# PDB_Sheet2.net
KiCad netlist of a schematic drawn in Altium Designer
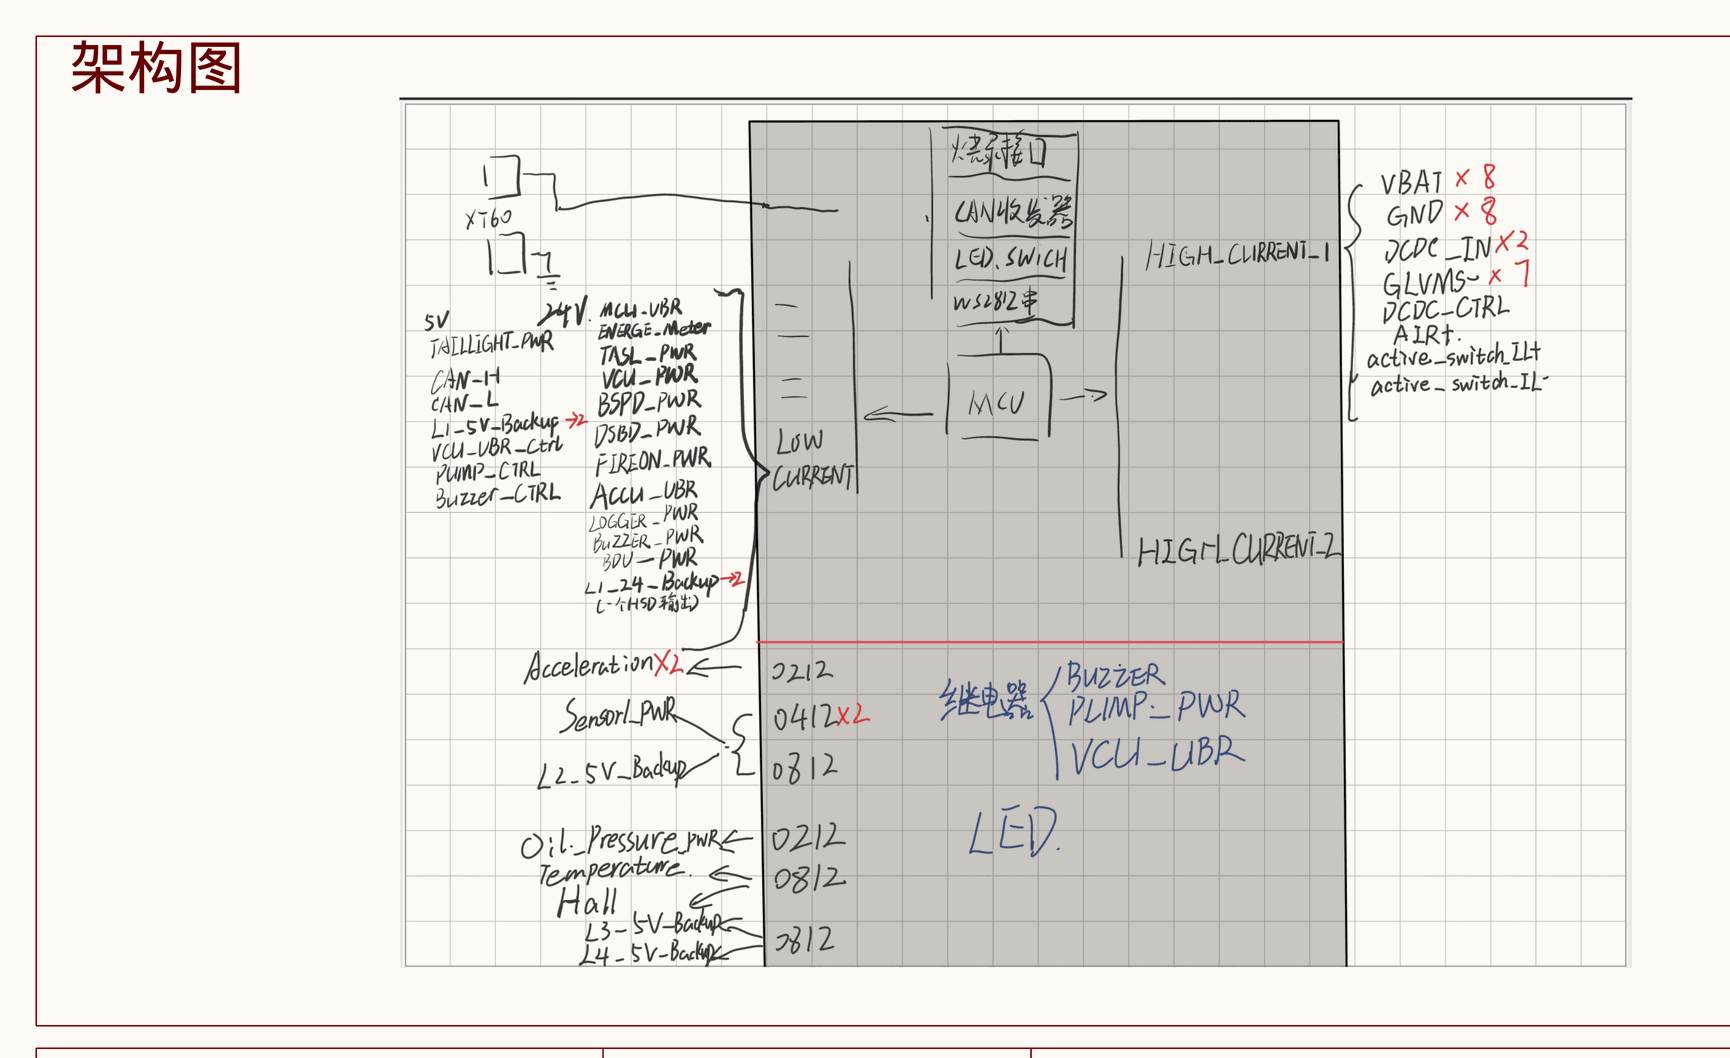
[diagram p0: PDB_Sheet2.SchDoc, top left]
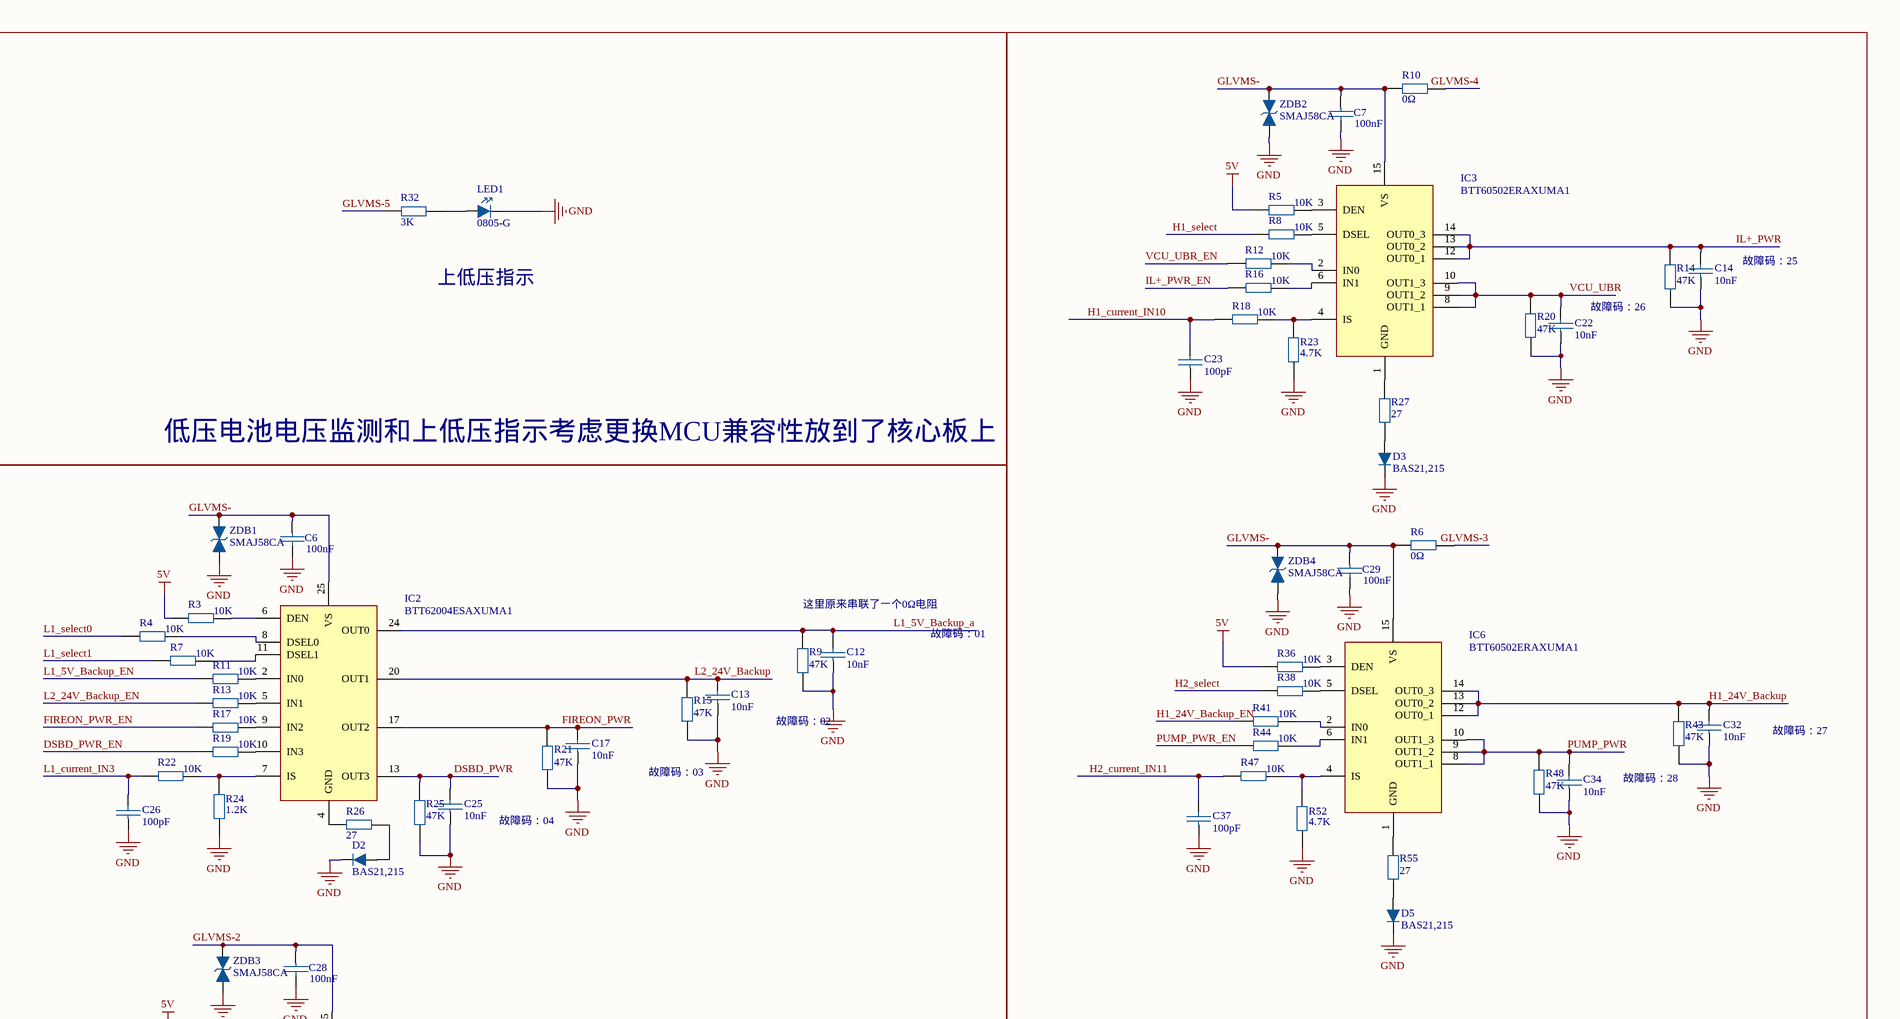
[diagram p1: PDB_Sheet2.SchDoc, top right]
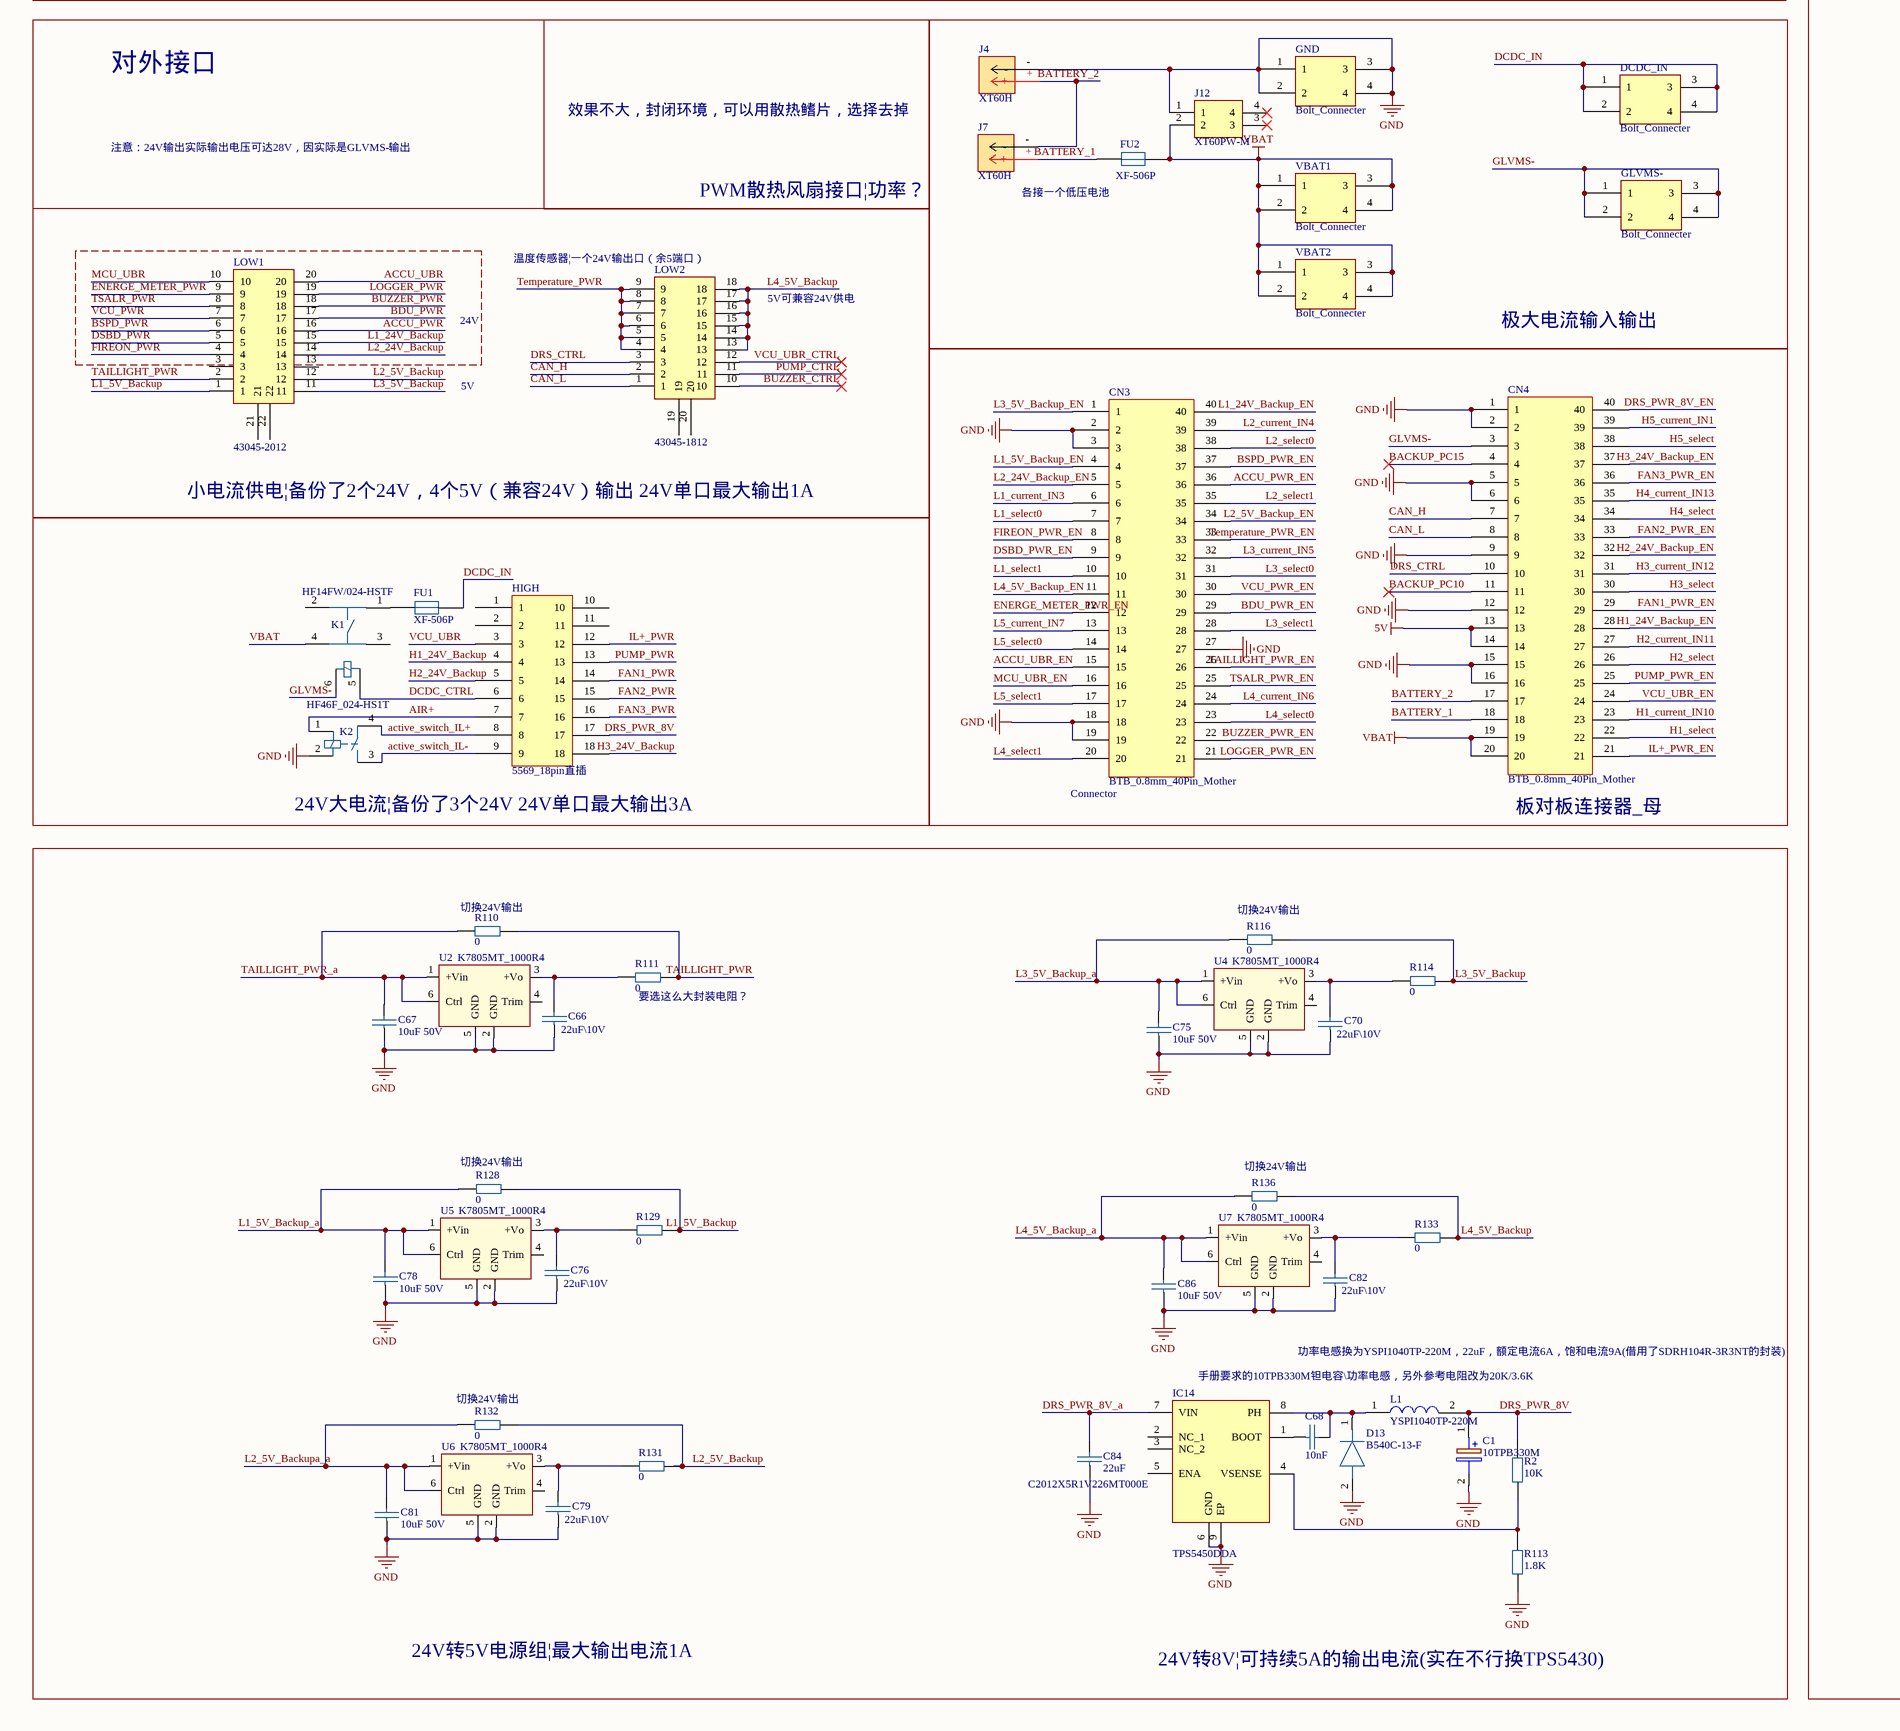
[diagram p2: PDB_Sheet2.SchDoc, bottom left]
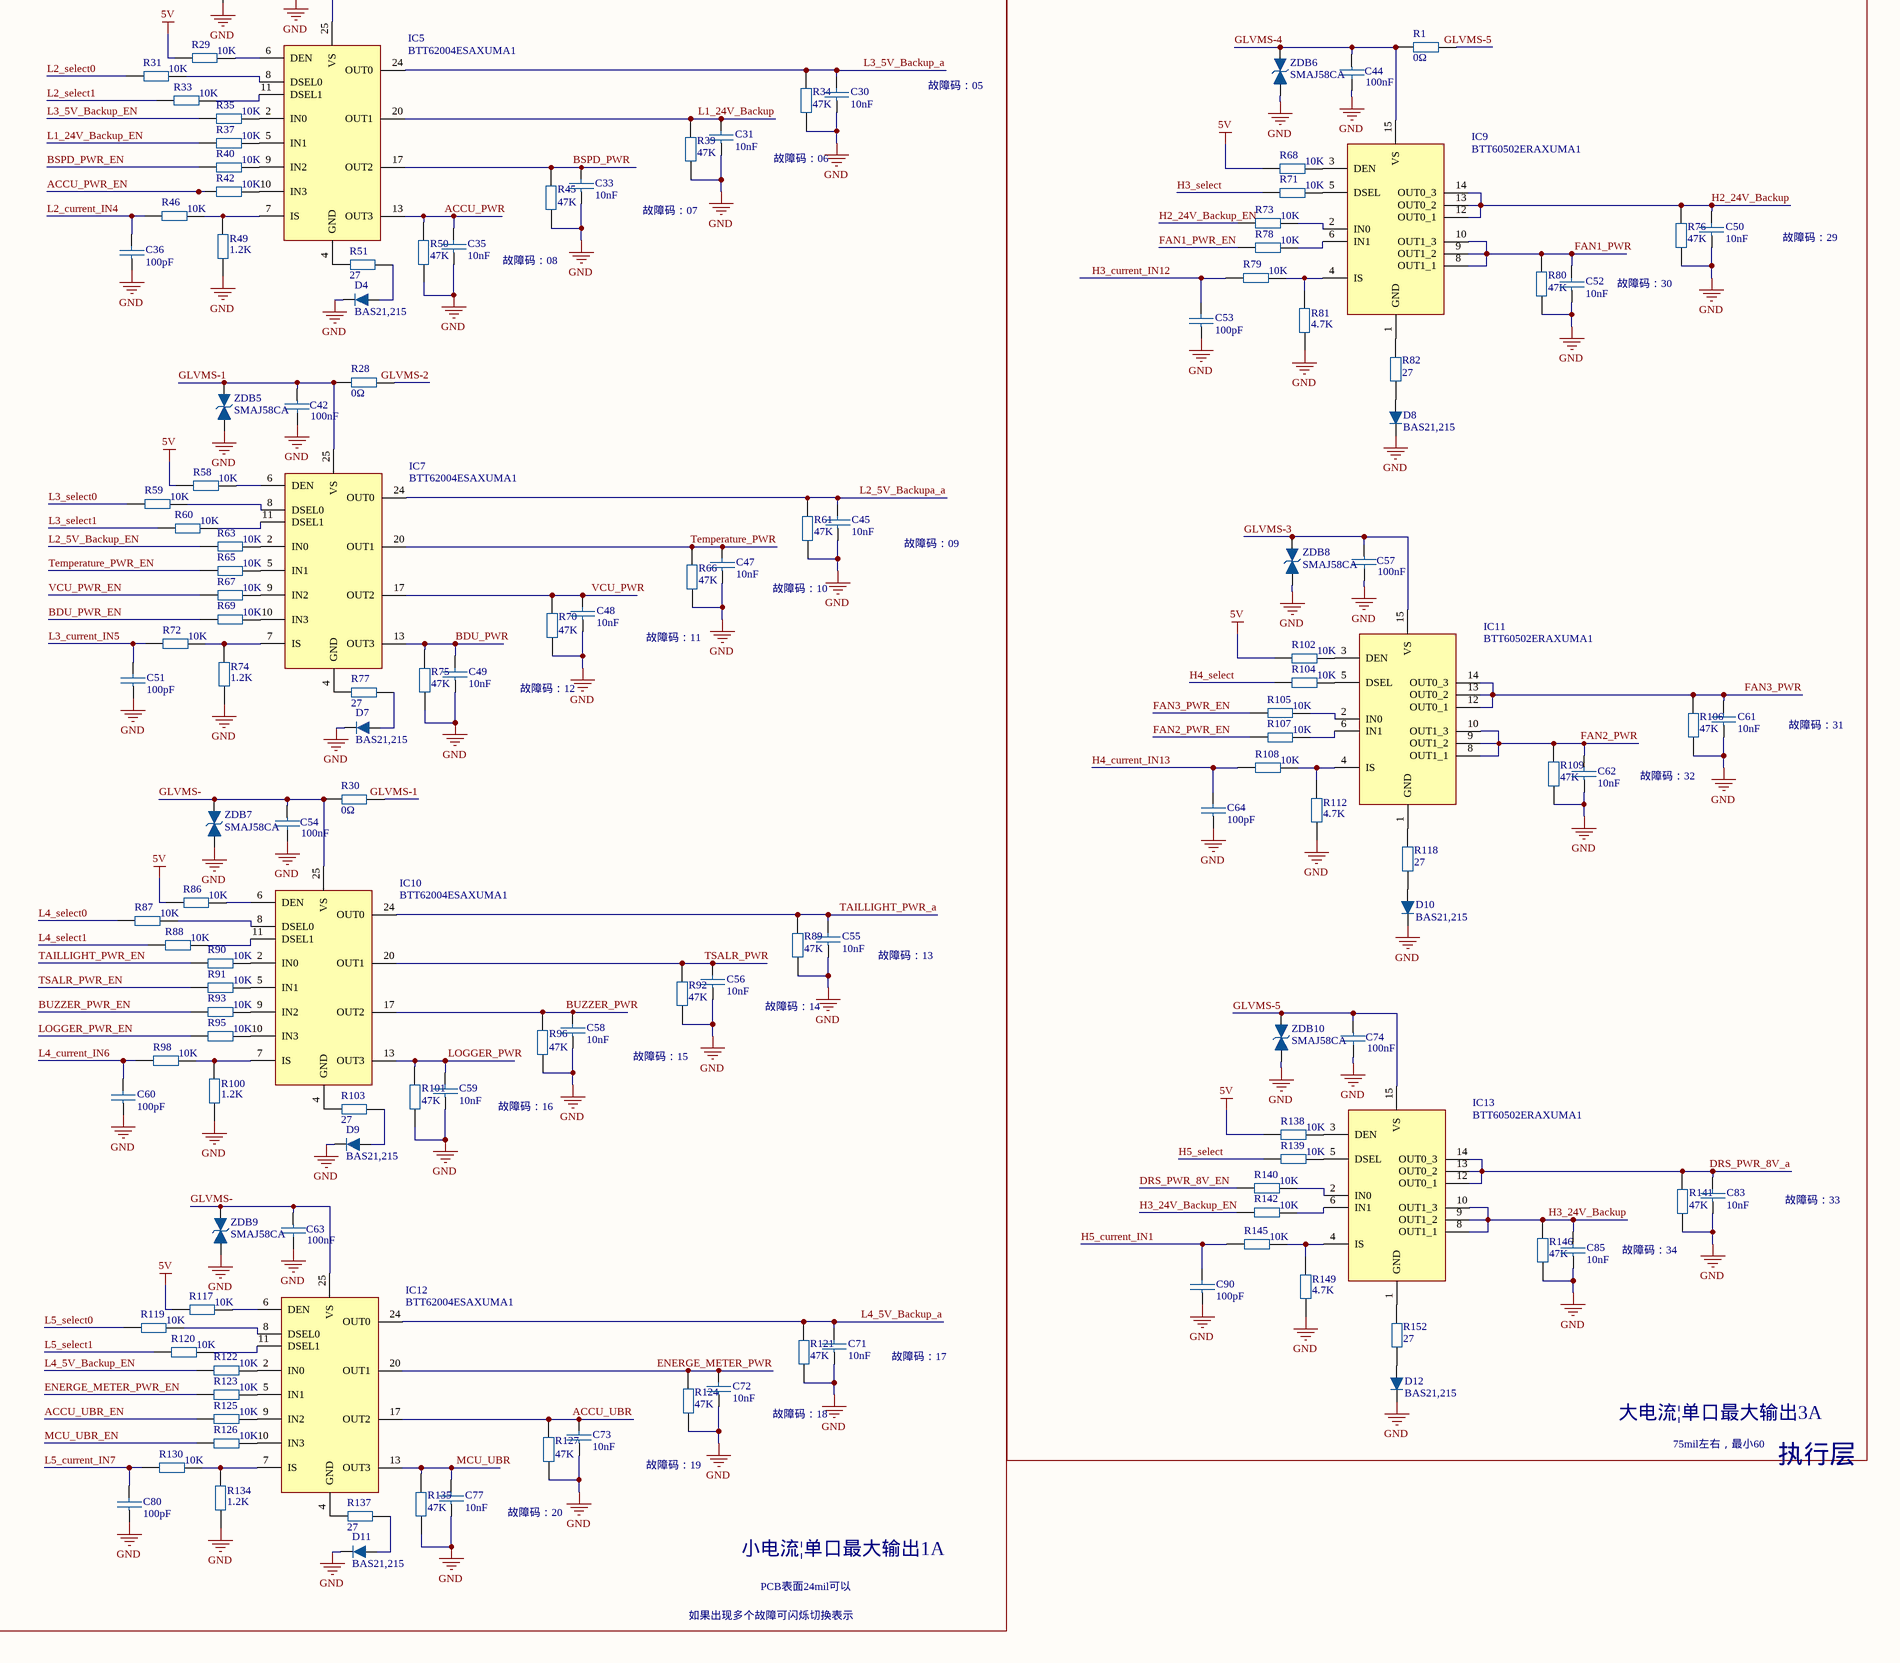
[diagram p3: PDB_Sheet2.SchDoc, bottom right]

(export (version "E")
  (design (tool "Eeschema 10.0.6"))
  (components
    (comp (ref "C1")
      (value "10TPB330M")
      (footprint "SamacSys:POSCAP_D12_D15_D15E_D2E_D2_D3L_D4")
      (description "Capacitor Polarised")
      (fields (field (name "MOUSER PART NUMBER") "667-10TPB330M"))
      (libsource (lib "*") (part "10TPB330M"))
    )
    (comp (ref "C6")
      (value "100nF")
      (footprint "CAPC1608X08N__0603CAPUNPOLE")
      (description "Std MLCC Cap")
      (libsource (lib "ResistorCapacitorInductor") (part "SMD_MLCC"))
    )
    (comp (ref "C7")
      (value "100nF")
      (footprint "CAPC1608X08N__0603CAPUNPOLE")
      (description "Std MLCC Cap")
      (libsource (lib "ResistorCapacitorInductor") (part "SMD_MLCC"))
    )
    (comp (ref "C12")
      (value "10nF")
      (footprint "CAPC1608X08N__0603CAPUNPOLE")
      (description "Std MLCC Cap")
      (libsource (lib "ResistorCapacitorInductor") (part "SMD_MLCC"))
    )
    (comp (ref "C13")
      (value "10nF")
      (footprint "CAPC1608X08N__0603CAPUNPOLE")
      (description "Std MLCC Cap")
      (libsource (lib "ResistorCapacitorInductor") (part "SMD_MLCC"))
    )
    (comp (ref "C14")
      (value "10nF")
      (footprint "CAPC1608X08N__0603CAPUNPOLE")
      (description "Std MLCC Cap")
      (libsource (lib "ResistorCapacitorInductor") (part "SMD_MLCC"))
    )
    (comp (ref "C17")
      (value "10nF")
      (footprint "CAPC1608X08N__0603CAPUNPOLE")
      (description "Std MLCC Cap")
      (libsource (lib "ResistorCapacitorInductor") (part "SMD_MLCC"))
    )
    (comp (ref "C22")
      (value "10nF")
      (footprint "CAPC1608X08N__0603CAPUNPOLE")
      (description "Std MLCC Cap")
      (libsource (lib "ResistorCapacitorInductor") (part "SMD_MLCC"))
    )
    (comp (ref "C23")
      (value "100pF")
      (footprint "CAPC1608X08N__0603CAPUNPOLE")
      (description "Std MLCC Cap")
      (libsource (lib "ResistorCapacitorInductor") (part "SMD_MLCC"))
    )
    (comp (ref "C25")
      (value "10nF")
      (footprint "CAPC1608X08N__0603CAPUNPOLE")
      (description "Std MLCC Cap")
      (libsource (lib "ResistorCapacitorInductor") (part "SMD_MLCC"))
    )
    (comp (ref "C26")
      (value "100pF")
      (footprint "CAPC1608X08N__0603CAPUNPOLE")
      (description "Std MLCC Cap")
      (libsource (lib "ResistorCapacitorInductor") (part "SMD_MLCC"))
    )
    (comp (ref "C28")
      (value "100nF")
      (footprint "CAPC1608X08N__0603CAPUNPOLE")
      (description "Std MLCC Cap")
      (libsource (lib "ResistorCapacitorInductor") (part "SMD_MLCC"))
    )
    (comp (ref "C29")
      (value "100nF")
      (footprint "CAPC1608X08N__0603CAPUNPOLE")
      (description "Std MLCC Cap")
      (libsource (lib "ResistorCapacitorInductor") (part "SMD_MLCC"))
    )
    (comp (ref "C30")
      (value "10nF")
      (footprint "CAPC1608X08N__0603CAPUNPOLE")
      (description "Std MLCC Cap")
      (libsource (lib "ResistorCapacitorInductor") (part "SMD_MLCC"))
    )
    (comp (ref "C31")
      (value "10nF")
      (footprint "CAPC1608X08N__0603CAPUNPOLE")
      (description "Std MLCC Cap")
      (libsource (lib "ResistorCapacitorInductor") (part "SMD_MLCC"))
    )
    (comp (ref "C32")
      (value "10nF")
      (footprint "CAPC1608X08N__0603CAPUNPOLE")
      (description "Std MLCC Cap")
      (libsource (lib "ResistorCapacitorInductor") (part "SMD_MLCC"))
    )
    (comp (ref "C33")
      (value "10nF")
      (footprint "CAPC1608X08N__0603CAPUNPOLE")
      (description "Std MLCC Cap")
      (libsource (lib "ResistorCapacitorInductor") (part "SMD_MLCC"))
    )
    (comp (ref "C34")
      (value "10nF")
      (footprint "CAPC1608X08N__0603CAPUNPOLE")
      (description "Std MLCC Cap")
      (libsource (lib "ResistorCapacitorInductor") (part "SMD_MLCC"))
    )
    (comp (ref "C35")
      (value "10nF")
      (footprint "CAPC1608X08N__0603CAPUNPOLE")
      (description "Std MLCC Cap")
      (libsource (lib "ResistorCapacitorInductor") (part "SMD_MLCC"))
    )
    (comp (ref "C36")
      (value "100pF")
      (footprint "CAPC1608X08N__0603CAPUNPOLE")
      (description "Std MLCC Cap")
      (libsource (lib "ResistorCapacitorInductor") (part "SMD_MLCC"))
    )
    (comp (ref "C37")
      (value "100pF")
      (footprint "CAPC1608X08N__0603CAPUNPOLE")
      (description "Std MLCC Cap")
      (libsource (lib "ResistorCapacitorInductor") (part "SMD_MLCC"))
    )
    (comp (ref "C42")
      (value "100nF")
      (footprint "CAPC1608X08N__0603CAPUNPOLE")
      (description "Std MLCC Cap")
      (libsource (lib "ResistorCapacitorInductor") (part "SMD_MLCC"))
    )
    (comp (ref "C44")
      (value "100nF")
      (footprint "CAPC1608X08N__0603CAPUNPOLE")
      (description "Std MLCC Cap")
      (libsource (lib "ResistorCapacitorInductor") (part "SMD_MLCC"))
    )
    (comp (ref "C45")
      (value "10nF")
      (footprint "CAPC1608X08N__0603CAPUNPOLE")
      (description "Std MLCC Cap")
      (libsource (lib "ResistorCapacitorInductor") (part "SMD_MLCC"))
    )
    (comp (ref "C47")
      (value "10nF")
      (footprint "CAPC1608X08N__0603CAPUNPOLE")
      (description "Std MLCC Cap")
      (libsource (lib "ResistorCapacitorInductor") (part "SMD_MLCC"))
    )
    (comp (ref "C48")
      (value "10nF")
      (footprint "CAPC1608X08N__0603CAPUNPOLE")
      (description "Std MLCC Cap")
      (libsource (lib "ResistorCapacitorInductor") (part "SMD_MLCC"))
    )
    (comp (ref "C49")
      (value "10nF")
      (footprint "CAPC1608X08N__0603CAPUNPOLE")
      (description "Std MLCC Cap")
      (libsource (lib "ResistorCapacitorInductor") (part "SMD_MLCC"))
    )
    (comp (ref "C50")
      (value "10nF")
      (footprint "CAPC1608X08N__0603CAPUNPOLE")
      (description "Std MLCC Cap")
      (libsource (lib "ResistorCapacitorInductor") (part "SMD_MLCC"))
    )
    (comp (ref "C51")
      (value "100pF")
      (footprint "CAPC1608X08N__0603CAPUNPOLE")
      (description "Std MLCC Cap")
      (libsource (lib "ResistorCapacitorInductor") (part "SMD_MLCC"))
    )
    (comp (ref "C52")
      (value "10nF")
      (footprint "CAPC1608X08N__0603CAPUNPOLE")
      (description "Std MLCC Cap")
      (libsource (lib "ResistorCapacitorInductor") (part "SMD_MLCC"))
    )
    (comp (ref "C53")
      (value "100pF")
      (footprint "CAPC1608X08N__0603CAPUNPOLE")
      (description "Std MLCC Cap")
      (libsource (lib "ResistorCapacitorInductor") (part "SMD_MLCC"))
    )
    (comp (ref "C54")
      (value "100nF")
      (footprint "CAPC1608X08N__0603CAPUNPOLE")
      (description "Std MLCC Cap")
      (libsource (lib "ResistorCapacitorInductor") (part "SMD_MLCC"))
    )
    (comp (ref "C55")
      (value "10nF")
      (footprint "CAPC1608X08N__0603CAPUNPOLE")
      (description "Std MLCC Cap")
      (libsource (lib "ResistorCapacitorInductor") (part "SMD_MLCC"))
    )
    (comp (ref "C56")
      (value "10nF")
      (footprint "CAPC1608X08N__0603CAPUNPOLE")
      (description "Std MLCC Cap")
      (libsource (lib "ResistorCapacitorInductor") (part "SMD_MLCC"))
    )
    (comp (ref "C57")
      (value "100nF")
      (footprint "CAPC1608X08N__0603CAPUNPOLE")
      (description "Std MLCC Cap")
      (libsource (lib "ResistorCapacitorInductor") (part "SMD_MLCC"))
    )
    (comp (ref "C58")
      (value "10nF")
      (footprint "CAPC1608X08N__0603CAPUNPOLE")
      (description "Std MLCC Cap")
      (libsource (lib "ResistorCapacitorInductor") (part "SMD_MLCC"))
    )
    (comp (ref "C59")
      (value "10nF")
      (footprint "CAPC1608X08N__0603CAPUNPOLE")
      (description "Std MLCC Cap")
      (libsource (lib "ResistorCapacitorInductor") (part "SMD_MLCC"))
    )
    (comp (ref "C60")
      (value "100pF")
      (footprint "CAPC1608X08N__0603CAPUNPOLE")
      (description "Std MLCC Cap")
      (libsource (lib "ResistorCapacitorInductor") (part "SMD_MLCC"))
    )
    (comp (ref "C61")
      (value "10nF")
      (footprint "CAPC1608X08N__0603CAPUNPOLE")
      (description "Std MLCC Cap")
      (libsource (lib "ResistorCapacitorInductor") (part "SMD_MLCC"))
    )
    (comp (ref "C62")
      (value "10nF")
      (footprint "CAPC1608X08N__0603CAPUNPOLE")
      (description "Std MLCC Cap")
      (libsource (lib "ResistorCapacitorInductor") (part "SMD_MLCC"))
    )
    (comp (ref "C63")
      (value "100nF")
      (footprint "CAPC1608X08N__0603CAPUNPOLE")
      (description "Std MLCC Cap")
      (libsource (lib "ResistorCapacitorInductor") (part "SMD_MLCC"))
    )
    (comp (ref "C64")
      (value "100pF")
      (footprint "CAPC1608X08N__0603CAPUNPOLE")
      (description "Std MLCC Cap")
      (libsource (lib "ResistorCapacitorInductor") (part "SMD_MLCC"))
    )
    (comp (ref "C66")
      (value "22u~{F}10V")
      (footprint "CAPC1608X08N__0603CAPUNPOLE")
      (description "Std MLCC Cap")
      (libsource (lib "ResistorCapacitorInductor") (part "SMD_MLCC"))
    )
    (comp (ref "C67")
      (value "10uF 50V")
      (footprint "CAPC3216X16N_1206CAPUNPOLE")
      (description "Std MLCC Cap")
      (libsource (lib "ResistorCapacitorInductor") (part "SMD_MLCC"))
    )
    (comp (ref "C68")
      (value "10nF")
      (footprint "CAPC1608X08N__0603CAPUNPOLE")
      (description "Std MLCC Cap")
      (libsource (lib "ResistorCapacitorInductor") (part "SMD_MLCC"))
    )
    (comp (ref "C70")
      (value "22u~{F}10V")
      (footprint "CAPC1608X08N__0603CAPUNPOLE")
      (description "Std MLCC Cap")
      (libsource (lib "ResistorCapacitorInductor") (part "SMD_MLCC"))
    )
    (comp (ref "C71")
      (value "10nF")
      (footprint "CAPC1608X08N__0603CAPUNPOLE")
      (description "Std MLCC Cap")
      (libsource (lib "ResistorCapacitorInductor") (part "SMD_MLCC"))
    )
    (comp (ref "C72")
      (value "10nF")
      (footprint "CAPC1608X08N__0603CAPUNPOLE")
      (description "Std MLCC Cap")
      (libsource (lib "ResistorCapacitorInductor") (part "SMD_MLCC"))
    )
    (comp (ref "C73")
      (value "10nF")
      (footprint "CAPC1608X08N__0603CAPUNPOLE")
      (description "Std MLCC Cap")
      (libsource (lib "ResistorCapacitorInductor") (part "SMD_MLCC"))
    )
    (comp (ref "C74")
      (value "100nF")
      (footprint "CAPC1608X08N__0603CAPUNPOLE")
      (description "Std MLCC Cap")
      (libsource (lib "ResistorCapacitorInductor") (part "SMD_MLCC"))
    )
    (comp (ref "C75")
      (value "10uF 50V")
      (footprint "CAPC3216X16N_1206CAPUNPOLE")
      (description "Std MLCC Cap")
      (libsource (lib "ResistorCapacitorInductor") (part "SMD_MLCC"))
    )
    (comp (ref "C76")
      (value "22u~{F}10V")
      (footprint "CAPC1608X08N__0603CAPUNPOLE")
      (description "Std MLCC Cap")
      (libsource (lib "ResistorCapacitorInductor") (part "SMD_MLCC"))
    )
    (comp (ref "C77")
      (value "10nF")
      (footprint "CAPC1608X08N__0603CAPUNPOLE")
      (description "Std MLCC Cap")
      (libsource (lib "ResistorCapacitorInductor") (part "SMD_MLCC"))
    )
    (comp (ref "C78")
      (value "10uF 50V")
      (footprint "CAPC3216X16N_1206CAPUNPOLE")
      (description "Std MLCC Cap")
      (libsource (lib "ResistorCapacitorInductor") (part "SMD_MLCC"))
    )
    (comp (ref "C79")
      (value "22u~{F}10V")
      (footprint "CAPC1608X08N__0603CAPUNPOLE")
      (description "Std MLCC Cap")
      (libsource (lib "ResistorCapacitorInductor") (part "SMD_MLCC"))
    )
    (comp (ref "C80")
      (value "100pF")
      (footprint "CAPC1608X08N__0603CAPUNPOLE")
      (description "Std MLCC Cap")
      (libsource (lib "ResistorCapacitorInductor") (part "SMD_MLCC"))
    )
    (comp (ref "C81")
      (value "10uF 50V")
      (footprint "CAPC3216X16N_1206CAPUNPOLE")
      (description "Std MLCC Cap")
      (libsource (lib "ResistorCapacitorInductor") (part "SMD_MLCC"))
    )
    (comp (ref "C82")
      (value "22u~{F}10V")
      (footprint "CAPC1608X08N__0603CAPUNPOLE")
      (description "Std MLCC Cap")
      (libsource (lib "ResistorCapacitorInductor") (part "SMD_MLCC"))
    )
    (comp (ref "C83")
      (value "10nF")
      (footprint "CAPC1608X08N__0603CAPUNPOLE")
      (description "Std MLCC Cap")
      (libsource (lib "ResistorCapacitorInductor") (part "SMD_MLCC"))
    )
    (comp (ref "C84")
      (value "22uF")
      (footprint "CAPC2012X06N__0805CAPUNPOLE")
      (description "Std MLCC Cap")
      (libsource (lib "ResistorCapacitorInductor") (part "SMD_MLCC"))
    )
    (comp (ref "C85")
      (value "10nF")
      (footprint "CAPC1608X08N__0603CAPUNPOLE")
      (description "Std MLCC Cap")
      (libsource (lib "ResistorCapacitorInductor") (part "SMD_MLCC"))
    )
    (comp (ref "C86")
      (value "10uF 50V")
      (footprint "CAPC3216X16N_1206CAPUNPOLE")
      (description "Std MLCC Cap")
      (libsource (lib "ResistorCapacitorInductor") (part "SMD_MLCC"))
    )
    (comp (ref "C90")
      (value "100pF")
      (footprint "CAPC1608X08N__0603CAPUNPOLE")
      (description "Std MLCC Cap")
      (libsource (lib "ResistorCapacitorInductor") (part "SMD_MLCC"))
    )
    (comp (ref "CN3")
      (value "BTB_0.8mm_40Pin_Mother")
      (footprint "BTB_0.8mm_40PIN_M")
      (fields (field (name "SYSTEM") "Connector"))
      (libsource (lib "Connector") (part "BTB_0.8mm_40Pin_Mother"))
    )
    (comp (ref "CN4")
      (value "BTB_0.8mm_40Pin_Mother")
      (footprint "BTB_0.8mm_40PIN_M")
      (libsource (lib "Connector") (part "BTB_0.8mm_40Pin_Mother"))
    )
    (comp (ref "D2")
      (value "BAS21,215")
      (footprint "BAS21215")
      (description "Diode")
      (fields (field (name "MOUSER PART NUMBER") "771-BAS21-T/R"))
      (libsource (lib "Diodes") (part "BAS21,215"))
    )
    (comp (ref "D3")
      (value "BAS21,215")
      (footprint "BAS21215")
      (description "Diode")
      (fields (field (name "MOUSER PART NUMBER") "771-BAS21-T/R"))
      (libsource (lib "Diodes") (part "BAS21,215"))
    )
    (comp (ref "D4")
      (value "BAS21,215")
      (footprint "BAS21215")
      (description "Diode")
      (fields (field (name "MOUSER PART NUMBER") "771-BAS21-T/R"))
      (libsource (lib "Diodes") (part "BAS21,215"))
    )
    (comp (ref "D5")
      (value "BAS21,215")
      (footprint "BAS21215")
      (description "Diode")
      (fields (field (name "MOUSER PART NUMBER") "771-BAS21-T/R"))
      (libsource (lib "Diodes") (part "BAS21,215"))
    )
    (comp (ref "D7")
      (value "BAS21,215")
      (footprint "BAS21215")
      (description "Diode")
      (fields (field (name "MOUSER PART NUMBER") "771-BAS21-T/R"))
      (libsource (lib "Diodes") (part "BAS21,215"))
    )
    (comp (ref "D8")
      (value "BAS21,215")
      (footprint "BAS21215")
      (description "Diode")
      (fields (field (name "MOUSER PART NUMBER") "771-BAS21-T/R"))
      (libsource (lib "Diodes") (part "BAS21,215"))
    )
    (comp (ref "D9")
      (value "BAS21,215")
      (footprint "BAS21215")
      (description "Diode")
      (fields (field (name "MOUSER PART NUMBER") "771-BAS21-T/R"))
      (libsource (lib "Diodes") (part "BAS21,215"))
    )
    (comp (ref "D10")
      (value "BAS21,215")
      (footprint "BAS21215")
      (description "Diode")
      (fields (field (name "MOUSER PART NUMBER") "771-BAS21-T/R"))
      (libsource (lib "Diodes") (part "BAS21,215"))
    )
    (comp (ref "D11")
      (value "BAS21,215")
      (footprint "BAS21215")
      (description "Diode")
      (fields (field (name "MOUSER PART NUMBER") "771-BAS21-T/R"))
      (libsource (lib "Diodes") (part "BAS21,215"))
    )
    (comp (ref "D12")
      (value "BAS21,215")
      (footprint "BAS21215")
      (description "Diode")
      (fields (field (name "MOUSER PART NUMBER") "771-BAS21-T/R"))
      (libsource (lib "Diodes") (part "BAS21,215"))
    )
    (comp (ref "D13")
      (value "B540C-13-F")
      (footprint "DIOM7959X250N")
      (description "Diode")
      (fields (field (name "MOUSER PART NUMBER") "621-B540C-F"))
      (libsource (lib "Diodes") (part "B540C-13-F"))
    )
    (comp (ref "DCDC_IN")
      (value "Bolt_Connecter")
      (footprint "Bolt_Connecter")
      (libsource (lib "Connector") (part "Bolt_Connecter"))
    )
    (comp (ref "FU1")
      (value "XF-506P")
      (footprint "XF-506P")
      (description "小型汽车插片保险丝座")
      (libsource (lib "ResistorCapacitorInductor") (part "XF-506P"))
    )
    (comp (ref "FU2")
      (value "XF-506P")
      (footprint "XF-506P")
      (description "小型汽车插片保险丝座")
      (libsource (lib "ResistorCapacitorInductor") (part "XF-506P"))
    )
    (comp (ref "GLVMS-")
      (value "Bolt_Connecter")
      (footprint "Bolt_Connecter")
      (libsource (lib "Connector") (part "Bolt_Connecter"))
    )
    (comp (ref "GND")
      (value "Bolt_Connecter")
      (footprint "Bolt_Connecter")
      (libsource (lib "Connector") (part "Bolt_Connecter"))
    )
    (comp (ref "HIGH")
      (value "5569_18pin直插")
      (footprint "5569_18Pin")
      (libsource (lib "Connector") (part "5569_18pin直插"))
    )
    (comp (ref "IC2")
      (value "BTT62004ESAXUMA1")
      (footprint "PG-TSDSO-24")
      (description "Integrated Circuit")
      (fields (field (name "MOUSER PART NUMBER") "726-BTT62004ESAXUMA1"))
      (libsource (lib "GateDrivers") (part "BTT62004ESAXUMA1"))
    )
    (comp (ref "IC3")
      (value "BTT60502ERAXUMA1")
      (footprint "PG-TDSO-14")
      (description "Integrated Circuit")
      (fields (field (name "MOUSER PART NUMBER") "726-BTT60502ERAXUMA1"))
      (libsource (lib "GateDrivers") (part "BTT60502ERAXUMA1"))
    )
    (comp (ref "IC5")
      (value "BTT62004ESAXUMA1")
      (footprint "PG-TSDSO-24")
      (description "Integrated Circuit")
      (fields (field (name "MOUSER PART NUMBER") "726-BTT62004ESAXUMA1"))
      (libsource (lib "GateDrivers") (part "BTT62004ESAXUMA1"))
    )
    (comp (ref "IC6")
      (value "BTT60502ERAXUMA1")
      (footprint "PG-TDSO-14")
      (description "Integrated Circuit")
      (fields (field (name "MOUSER PART NUMBER") "726-BTT60502ERAXUMA1"))
      (libsource (lib "GateDrivers") (part "BTT60502ERAXUMA1"))
    )
    (comp (ref "IC7")
      (value "BTT62004ESAXUMA1")
      (footprint "PG-TSDSO-24")
      (description "Integrated Circuit")
      (fields (field (name "MOUSER PART NUMBER") "726-BTT62004ESAXUMA1"))
      (libsource (lib "GateDrivers") (part "BTT62004ESAXUMA1"))
    )
    (comp (ref "IC9")
      (value "BTT60502ERAXUMA1")
      (footprint "PG-TDSO-14")
      (description "Integrated Circuit")
      (fields (field (name "MOUSER PART NUMBER") "726-BTT60502ERAXUMA1"))
      (libsource (lib "GateDrivers") (part "BTT60502ERAXUMA1"))
    )
    (comp (ref "IC10")
      (value "BTT62004ESAXUMA1")
      (footprint "PG-TSDSO-24")
      (description "Integrated Circuit")
      (fields (field (name "MOUSER PART NUMBER") "726-BTT62004ESAXUMA1"))
      (libsource (lib "GateDrivers") (part "BTT62004ESAXUMA1"))
    )
    (comp (ref "IC11")
      (value "BTT60502ERAXUMA1")
      (footprint "PG-TDSO-14")
      (description "Integrated Circuit")
      (fields (field (name "MOUSER PART NUMBER") "726-BTT60502ERAXUMA1"))
      (libsource (lib "GateDrivers") (part "BTT60502ERAXUMA1"))
    )
    (comp (ref "IC12")
      (value "BTT62004ESAXUMA1")
      (footprint "PG-TSDSO-24")
      (description "Integrated Circuit")
      (fields (field (name "MOUSER PART NUMBER") "726-BTT62004ESAXUMA1"))
      (libsource (lib "GateDrivers") (part "BTT62004ESAXUMA1"))
    )
    (comp (ref "IC13")
      (value "BTT60502ERAXUMA1")
      (footprint "PG-TDSO-14")
      (description "Integrated Circuit")
      (fields (field (name "MOUSER PART NUMBER") "726-BTT60502ERAXUMA1"))
      (libsource (lib "GateDrivers") (part "BTT60502ERAXUMA1"))
    )
    (comp (ref "IC14")
      (value "TPS5450DDA")
      (footprint "DCDC_LDO:SOIC127P600X170-9N")
      (description "Integrated Circuit")
      (fields (field (name "MOUSER PART NUMBER") "595-TPS5450DDA"))
      (libsource (lib "DCDC_LDO") (part "TPS5450DDA"))
    )
    (comp (ref "J4")
      (value "XT60H")
      (footprint "AMASS_XT60_NOMAL")
      (libsource (lib "Connector") (part "AmassXTxx_Connector"))
    )
    (comp (ref "J7")
      (value "XT60H")
      (footprint "AMASS_XT60_NOMAL")
      (libsource (lib "Connector") (part "AmassXTxx_Connector"))
    )
    (comp (ref "J12")
      (value "XT60PW-M")
      (footprint "XT60PWM")
      (description "Connector")
      (libsource (lib "Connector") (part "XT60PW-M"))
    )
    (comp (ref "K1")
      (value "HF14FW/024-HSTF")
      (footprint "HF14FW005HPTF")
      (description "Relay or Contactor")
      (libsource (lib "Relay") (part "HF14FW/024-HSTF"))
    )
    (comp (ref "K2")
      (value "HF46F_024-HS1T")
      (footprint "HF46F024HS1T")
      (description "Relay or Contactor")
      (fields (field (name "MANUFACTURER_PART_NUMBER") "HF46F/024-HS1T"))
      (libsource (lib "Relay") (part "HF46F_024-HS1T"))
    )
    (comp (ref "L1")
      (value "YSPI1040TP-220M")
      (footprint "SamacSys:SDRH104R3R3NT")
      (description "Inductor")
      (fields (field (name "MANUFACTURER_PART_NUMBER") "SDRH104R-3R3NT"))
      (libsource (lib "*") (part "SDRH104R-3R3NT"))
    )
    (comp (ref "LED1")
      (value "0805-G")
      (footprint "DIOC2012X11N__0805DIO")
      (description "Light Emitting Diode")
      (libsource (lib "Diodes") (part "LED"))
    )
    (comp (ref "LOW1")
      (value "43045-2012")
      (footprint "Connector:43045-20YY_121314")
      (description "Connector")
      (fields (field (name "MOUSER PART NUMBER") "538-43045-2012"))
      (libsource (lib "Connector") (part "43045-2012"))
    )
    (comp (ref "LOW2")
      (value "43045-1812")
      (footprint "43045-18YY_121314")
      (description "Connector")
      (fields (field (name "MOUSER PART NUMBER") "538-43045-1812"))
      (libsource (lib "Connector") (part "43045-1812"))
    )
    (comp (ref "R1")
      (value "0Ω")
      (footprint "RESC6432X06N__2512RES")
      (description "Std Resistor")
      (libsource (lib "ResistorCapacitorInductor") (part "SMD_Resistor"))
    )
    (comp (ref "R2")
      (value "10K")
      (footprint "RESC1608X04N_0603RES")
      (description "Std Resistor")
      (libsource (lib "ResistorCapacitorInductor") (part "SMD_Resistor"))
    )
    (comp (ref "R3")
      (value "10K")
      (footprint "RESC1608X04N_0603RES")
      (description "Std Resistor")
      (libsource (lib "ResistorCapacitorInductor") (part "SMD_Resistor"))
    )
    (comp (ref "R4")
      (value "10K")
      (footprint "RESC1608X04N_0603RES")
      (description "Std Resistor")
      (libsource (lib "ResistorCapacitorInductor") (part "SMD_Resistor"))
    )
    (comp (ref "R5")
      (value "10K")
      (footprint "RESC1608X04N_0603RES")
      (description "Std Resistor")
      (libsource (lib "ResistorCapacitorInductor") (part "SMD_Resistor"))
    )
    (comp (ref "R6")
      (value "0Ω")
      (footprint "RESC6432X06N__2512RES")
      (description "Std Resistor")
      (libsource (lib "ResistorCapacitorInductor") (part "SMD_Resistor"))
    )
    (comp (ref "R7")
      (value "10K")
      (footprint "RESC1608X04N_0603RES")
      (description "Std Resistor")
      (libsource (lib "ResistorCapacitorInductor") (part "SMD_Resistor"))
    )
    (comp (ref "R8")
      (value "10K")
      (footprint "RESC1608X04N_0603RES")
      (description "Std Resistor")
      (libsource (lib "ResistorCapacitorInductor") (part "SMD_Resistor"))
    )
    (comp (ref "R9")
      (value "47K")
      (footprint "RESC1608X04N_0603RES")
      (description "Std Resistor")
      (libsource (lib "ResistorCapacitorInductor") (part "SMD_Resistor"))
    )
    (comp (ref "R10")
      (value "0Ω")
      (footprint "RESC6432X06N__2512RES")
      (description "Std Resistor")
      (libsource (lib "ResistorCapacitorInductor") (part "SMD_Resistor"))
    )
    (comp (ref "R11")
      (value "10K")
      (footprint "RESC1608X04N_0603RES")
      (description "Std Resistor")
      (libsource (lib "ResistorCapacitorInductor") (part "SMD_Resistor"))
    )
    (comp (ref "R12")
      (value "10K")
      (footprint "RESC1608X04N_0603RES")
      (description "Std Resistor")
      (libsource (lib "ResistorCapacitorInductor") (part "SMD_Resistor"))
    )
    (comp (ref "R13")
      (value "10K")
      (footprint "RESC1608X04N_0603RES")
      (description "Std Resistor")
      (libsource (lib "ResistorCapacitorInductor") (part "SMD_Resistor"))
    )
    (comp (ref "R14")
      (value "47K")
      (footprint "RESC1608X04N_0603RES")
      (description "Std Resistor")
      (libsource (lib "ResistorCapacitorInductor") (part "SMD_Resistor"))
    )
    (comp (ref "R15")
      (value "47K")
      (footprint "RESC1608X04N_0603RES")
      (description "Std Resistor")
      (libsource (lib "ResistorCapacitorInductor") (part "SMD_Resistor"))
    )
    (comp (ref "R16")
      (value "10K")
      (footprint "RESC1608X04N_0603RES")
      (description "Std Resistor")
      (libsource (lib "ResistorCapacitorInductor") (part "SMD_Resistor"))
    )
    (comp (ref "R17")
      (value "10K")
      (footprint "RESC1608X04N_0603RES")
      (description "Std Resistor")
      (libsource (lib "ResistorCapacitorInductor") (part "SMD_Resistor"))
    )
    (comp (ref "R18")
      (value "10K")
      (footprint "RESC1608X04N_0603RES")
      (description "Std Resistor")
      (libsource (lib "ResistorCapacitorInductor") (part "SMD_Resistor"))
    )
    (comp (ref "R19")
      (value "10K")
      (footprint "RESC1608X04N_0603RES")
      (description "Std Resistor")
      (libsource (lib "ResistorCapacitorInductor") (part "SMD_Resistor"))
    )
    (comp (ref "R20")
      (value "47K")
      (footprint "RESC1608X04N_0603RES")
      (description "Std Resistor")
      (libsource (lib "ResistorCapacitorInductor") (part "SMD_Resistor"))
    )
    (comp (ref "R21")
      (value "47K")
      (footprint "RESC1608X04N_0603RES")
      (description "Std Resistor")
      (libsource (lib "ResistorCapacitorInductor") (part "SMD_Resistor"))
    )
    (comp (ref "R22")
      (value "10K")
      (footprint "RESC1608X04N_0603RES")
      (description "Std Resistor")
      (libsource (lib "ResistorCapacitorInductor") (part "SMD_Resistor"))
    )
    (comp (ref "R23")
      (value "4.7K")
      (footprint "RESC1608X04N_0603RES")
      (description "Std Resistor")
      (libsource (lib "ResistorCapacitorInductor") (part "SMD_Resistor"))
    )
    (comp (ref "R24")
      (value "1.2K")
      (footprint "RESC1608X04N_0603RES")
      (description "Std Resistor")
      (libsource (lib "ResistorCapacitorInductor") (part "SMD_Resistor"))
    )
    (comp (ref "R25")
      (value "47K")
      (footprint "RESC1608X04N_0603RES")
      (description "Std Resistor")
      (libsource (lib "ResistorCapacitorInductor") (part "SMD_Resistor"))
    )
    (comp (ref "R26")
      (value "27")
      (footprint "RESC1608X04N_0603RES")
      (description "Std Resistor")
      (libsource (lib "ResistorCapacitorInductor") (part "SMD_Resistor"))
    )
    (comp (ref "R27")
      (value "27")
      (footprint "RESC1608X04N_0603RES")
      (description "Std Resistor")
      (libsource (lib "ResistorCapacitorInductor") (part "SMD_Resistor"))
    )
    (comp (ref "R28")
      (value "0Ω")
      (footprint "RESC6432X06N__2512RES")
      (description "Std Resistor")
      (libsource (lib "ResistorCapacitorInductor") (part "SMD_Resistor"))
    )
    (comp (ref "R29")
      (value "10K")
      (footprint "RESC1608X04N_0603RES")
      (description "Std Resistor")
      (libsource (lib "ResistorCapacitorInductor") (part "SMD_Resistor"))
    )
    (comp (ref "R30")
      (value "0Ω")
      (footprint "RESC6432X06N__2512RES")
      (description "Std Resistor")
      (libsource (lib "ResistorCapacitorInductor") (part "SMD_Resistor"))
    )
    (comp (ref "R31")
      (value "10K")
      (footprint "RESC1608X04N_0603RES")
      (description "Std Resistor")
      (libsource (lib "ResistorCapacitorInductor") (part "SMD_Resistor"))
    )
    (comp (ref "R32")
      (value "3K")
      (footprint "RESC1608X04N_0603RES")
      (description "Std Resistor")
      (libsource (lib "ResistorCapacitorInductor") (part "SMD_Resistor"))
    )
    (comp (ref "R33")
      (value "10K")
      (footprint "RESC1608X04N_0603RES")
      (description "Std Resistor")
      (libsource (lib "ResistorCapacitorInductor") (part "SMD_Resistor"))
    )
    (comp (ref "R34")
      (value "47K")
      (footprint "RESC1608X04N_0603RES")
      (description "Std Resistor")
      (libsource (lib "ResistorCapacitorInductor") (part "SMD_Resistor"))
    )
    (comp (ref "R35")
      (value "10K")
      (footprint "RESC1608X04N_0603RES")
      (description "Std Resistor")
      (libsource (lib "ResistorCapacitorInductor") (part "SMD_Resistor"))
    )
    (comp (ref "R36")
      (value "10K")
      (footprint "RESC1608X04N_0603RES")
      (description "Std Resistor")
      (libsource (lib "ResistorCapacitorInductor") (part "SMD_Resistor"))
    )
    (comp (ref "R37")
      (value "10K")
      (footprint "RESC1608X04N_0603RES")
      (description "Std Resistor")
      (libsource (lib "ResistorCapacitorInductor") (part "SMD_Resistor"))
    )
    (comp (ref "R38")
      (value "10K")
      (footprint "RESC1608X04N_0603RES")
      (description "Std Resistor")
      (libsource (lib "ResistorCapacitorInductor") (part "SMD_Resistor"))
    )
    (comp (ref "R39")
      (value "47K")
      (footprint "RESC1608X04N_0603RES")
      (description "Std Resistor")
      (libsource (lib "ResistorCapacitorInductor") (part "SMD_Resistor"))
    )
    (comp (ref "R40")
      (value "10K")
      (footprint "RESC1608X04N_0603RES")
      (description "Std Resistor")
      (libsource (lib "ResistorCapacitorInductor") (part "SMD_Resistor"))
    )
    (comp (ref "R41")
      (value "10K")
      (footprint "RESC1608X04N_0603RES")
      (description "Std Resistor")
      (libsource (lib "ResistorCapacitorInductor") (part "SMD_Resistor"))
    )
    (comp (ref "R42")
      (value "10K")
      (footprint "RESC1608X04N_0603RES")
      (description "Std Resistor")
      (libsource (lib "ResistorCapacitorInductor") (part "SMD_Resistor"))
    )
    (comp (ref "R43")
      (value "47K")
      (footprint "RESC1608X04N_0603RES")
      (description "Std Resistor")
      (libsource (lib "ResistorCapacitorInductor") (part "SMD_Resistor"))
    )
    (comp (ref "R44")
      (value "10K")
      (footprint "RESC1608X04N_0603RES")
      (description "Std Resistor")
      (libsource (lib "ResistorCapacitorInductor") (part "SMD_Resistor"))
    )
    (comp (ref "R45")
      (value "47K")
      (footprint "RESC1608X04N_0603RES")
      (description "Std Resistor")
      (libsource (lib "ResistorCapacitorInductor") (part "SMD_Resistor"))
    )
    (comp (ref "R46")
      (value "10K")
      (footprint "RESC1608X04N_0603RES")
      (description "Std Resistor")
      (libsource (lib "ResistorCapacitorInductor") (part "SMD_Resistor"))
    )
    (comp (ref "R47")
      (value "10K")
      (footprint "RESC1608X04N_0603RES")
      (description "Std Resistor")
      (libsource (lib "ResistorCapacitorInductor") (part "SMD_Resistor"))
    )
    (comp (ref "R48")
      (value "47K")
      (footprint "RESC1608X04N_0603RES")
      (description "Std Resistor")
      (libsource (lib "ResistorCapacitorInductor") (part "SMD_Resistor"))
    )
    (comp (ref "R49")
      (value "1.2K")
      (footprint "RESC1608X04N_0603RES")
      (description "Std Resistor")
      (libsource (lib "ResistorCapacitorInductor") (part "SMD_Resistor"))
    )
    (comp (ref "R50")
      (value "47K")
      (footprint "RESC1608X04N_0603RES")
      (description "Std Resistor")
      (libsource (lib "ResistorCapacitorInductor") (part "SMD_Resistor"))
    )
    (comp (ref "R51")
      (value "27")
      (footprint "RESC1608X04N_0603RES")
      (description "Std Resistor")
      (libsource (lib "ResistorCapacitorInductor") (part "SMD_Resistor"))
    )
    (comp (ref "R52")
      (value "4.7K")
      (footprint "RESC1608X04N_0603RES")
      (description "Std Resistor")
      (libsource (lib "ResistorCapacitorInductor") (part "SMD_Resistor"))
    )
    (comp (ref "R55")
      (value "27")
      (footprint "RESC1608X04N_0603RES")
      (description "Std Resistor")
      (libsource (lib "ResistorCapacitorInductor") (part "SMD_Resistor"))
    )
    (comp (ref "R58")
      (value "10K")
      (footprint "RESC1608X04N_0603RES")
      (description "Std Resistor")
      (libsource (lib "ResistorCapacitorInductor") (part "SMD_Resistor"))
    )
    (comp (ref "R59")
      (value "10K")
      (footprint "RESC1608X04N_0603RES")
      (description "Std Resistor")
      (libsource (lib "ResistorCapacitorInductor") (part "SMD_Resistor"))
    )
    (comp (ref "R60")
      (value "10K")
      (footprint "RESC1608X04N_0603RES")
      (description "Std Resistor")
      (libsource (lib "ResistorCapacitorInductor") (part "SMD_Resistor"))
    )
    (comp (ref "R61")
      (value "47K")
      (footprint "RESC1608X04N_0603RES")
      (description "Std Resistor")
      (libsource (lib "ResistorCapacitorInductor") (part "SMD_Resistor"))
    )
    (comp (ref "R63")
      (value "10K")
      (footprint "RESC1608X04N_0603RES")
      (description "Std Resistor")
      (libsource (lib "ResistorCapacitorInductor") (part "SMD_Resistor"))
    )
    (comp (ref "R65")
      (value "10K")
      (footprint "RESC1608X04N_0603RES")
      (description "Std Resistor")
      (libsource (lib "ResistorCapacitorInductor") (part "SMD_Resistor"))
    )
    (comp (ref "R66")
      (value "47K")
      (footprint "RESC1608X04N_0603RES")
      (description "Std Resistor")
      (libsource (lib "ResistorCapacitorInductor") (part "SMD_Resistor"))
    )
    (comp (ref "R67")
      (value "10K")
      (footprint "RESC1608X04N_0603RES")
      (description "Std Resistor")
      (libsource (lib "ResistorCapacitorInductor") (part "SMD_Resistor"))
    )
    (comp (ref "R68")
      (value "10K")
      (footprint "RESC1608X04N_0603RES")
      (description "Std Resistor")
      (libsource (lib "ResistorCapacitorInductor") (part "SMD_Resistor"))
    )
    (comp (ref "R69")
      (value "10K")
      (footprint "RESC1608X04N_0603RES")
      (description "Std Resistor")
      (libsource (lib "ResistorCapacitorInductor") (part "SMD_Resistor"))
    )
    (comp (ref "R70")
      (value "47K")
      (footprint "RESC1608X04N_0603RES")
      (description "Std Resistor")
      (libsource (lib "ResistorCapacitorInductor") (part "SMD_Resistor"))
    )
    (comp (ref "R71")
      (value "10K")
      (footprint "RESC1608X04N_0603RES")
      (description "Std Resistor")
      (libsource (lib "ResistorCapacitorInductor") (part "SMD_Resistor"))
    )
    (comp (ref "R72")
      (value "10K")
      (footprint "RESC1608X04N_0603RES")
      (description "Std Resistor")
      (libsource (lib "ResistorCapacitorInductor") (part "SMD_Resistor"))
    )
    (comp (ref "R73")
      (value "10K")
      (footprint "RESC1608X04N_0603RES")
      (description "Std Resistor")
      (libsource (lib "ResistorCapacitorInductor") (part "SMD_Resistor"))
    )
    (comp (ref "R74")
      (value "1.2K")
      (footprint "RESC1608X04N_0603RES")
      (description "Std Resistor")
      (libsource (lib "ResistorCapacitorInductor") (part "SMD_Resistor"))
    )
    (comp (ref "R75")
      (value "47K")
      (footprint "RESC1608X04N_0603RES")
      (description "Std Resistor")
      (libsource (lib "ResistorCapacitorInductor") (part "SMD_Resistor"))
    )
    (comp (ref "R76")
      (value "47K")
      (footprint "RESC1608X04N_0603RES")
      (description "Std Resistor")
      (libsource (lib "ResistorCapacitorInductor") (part "SMD_Resistor"))
    )
    (comp (ref "R77")
      (value "27")
      (footprint "RESC1608X04N_0603RES")
      (description "Std Resistor")
      (libsource (lib "ResistorCapacitorInductor") (part "SMD_Resistor"))
    )
    (comp (ref "R78")
      (value "10K")
      (footprint "RESC1608X04N_0603RES")
      (description "Std Resistor")
      (libsource (lib "ResistorCapacitorInductor") (part "SMD_Resistor"))
    )
    (comp (ref "R79")
      (value "10K")
      (footprint "RESC1608X04N_0603RES")
      (description "Std Resistor")
      (libsource (lib "ResistorCapacitorInductor") (part "SMD_Resistor"))
    )
    (comp (ref "R80")
      (value "47K")
      (footprint "RESC1608X04N_0603RES")
      (description "Std Resistor")
      (libsource (lib "ResistorCapacitorInductor") (part "SMD_Resistor"))
    )
    (comp (ref "R81")
      (value "4.7K")
      (footprint "RESC1608X04N_0603RES")
      (description "Std Resistor")
      (libsource (lib "ResistorCapacitorInductor") (part "SMD_Resistor"))
    )
    (comp (ref "R82")
      (value "27")
      (footprint "RESC1608X04N_0603RES")
      (description "Std Resistor")
      (libsource (lib "ResistorCapacitorInductor") (part "SMD_Resistor"))
    )
    (comp (ref "R86")
      (value "10K")
      (footprint "RESC1608X04N_0603RES")
      (description "Std Resistor")
      (libsource (lib "ResistorCapacitorInductor") (part "SMD_Resistor"))
    )
    (comp (ref "R87")
      (value "10K")
      (footprint "RESC1608X04N_0603RES")
      (description "Std Resistor")
      (libsource (lib "ResistorCapacitorInductor") (part "SMD_Resistor"))
    )
    (comp (ref "R88")
      (value "10K")
      (footprint "RESC1608X04N_0603RES")
      (description "Std Resistor")
      (libsource (lib "ResistorCapacitorInductor") (part "SMD_Resistor"))
    )
    (comp (ref "R89")
      (value "47K")
      (footprint "RESC1608X04N_0603RES")
      (description "Std Resistor")
      (libsource (lib "ResistorCapacitorInductor") (part "SMD_Resistor"))
    )
    (comp (ref "R90")
      (value "10K")
      (footprint "RESC1608X04N_0603RES")
      (description "Std Resistor")
      (libsource (lib "ResistorCapacitorInductor") (part "SMD_Resistor"))
    )
    (comp (ref "R91")
      (value "10K")
      (footprint "RESC1608X04N_0603RES")
      (description "Std Resistor")
      (libsource (lib "ResistorCapacitorInductor") (part "SMD_Resistor"))
    )
    (comp (ref "R92")
      (value "47K")
      (footprint "RESC1608X04N_0603RES")
      (description "Std Resistor")
      (libsource (lib "ResistorCapacitorInductor") (part "SMD_Resistor"))
    )
    (comp (ref "R93")
      (value "10K")
      (footprint "RESC1608X04N_0603RES")
      (description "Std Resistor")
      (libsource (lib "ResistorCapacitorInductor") (part "SMD_Resistor"))
    )
    (comp (ref "R95")
      (value "10K")
      (footprint "RESC1608X04N_0603RES")
      (description "Std Resistor")
      (libsource (lib "ResistorCapacitorInductor") (part "SMD_Resistor"))
    )
    (comp (ref "R96")
      (value "47K")
      (footprint "RESC1608X04N_0603RES")
      (description "Std Resistor")
      (libsource (lib "ResistorCapacitorInductor") (part "SMD_Resistor"))
    )
    (comp (ref "R98")
      (value "10K")
      (footprint "RESC1608X04N_0603RES")
      (description "Std Resistor")
      (libsource (lib "ResistorCapacitorInductor") (part "SMD_Resistor"))
    )
    (comp (ref "R100")
      (value "1.2K")
      (footprint "RESC1608X04N_0603RES")
      (description "Std Resistor")
      (libsource (lib "ResistorCapacitorInductor") (part "SMD_Resistor"))
    )
    (comp (ref "R101")
      (value "47K")
      (footprint "RESC1608X04N_0603RES")
      (description "Std Resistor")
      (libsource (lib "ResistorCapacitorInductor") (part "SMD_Resistor"))
    )
    (comp (ref "R102")
      (value "10K")
      (footprint "RESC1608X04N_0603RES")
      (description "Std Resistor")
      (libsource (lib "ResistorCapacitorInductor") (part "SMD_Resistor"))
    )
    (comp (ref "R103")
      (value "27")
      (footprint "RESC1608X04N_0603RES")
      (description "Std Resistor")
      (libsource (lib "ResistorCapacitorInductor") (part "SMD_Resistor"))
    )
    (comp (ref "R104")
      (value "10K")
      (footprint "RESC1608X04N_0603RES")
      (description "Std Resistor")
      (libsource (lib "ResistorCapacitorInductor") (part "SMD_Resistor"))
    )
    (comp (ref "R105")
      (value "10K")
      (footprint "RESC1608X04N_0603RES")
      (description "Std Resistor")
      (libsource (lib "ResistorCapacitorInductor") (part "SMD_Resistor"))
    )
    (comp (ref "R106")
      (value "47K")
      (footprint "RESC1608X04N_0603RES")
      (description "Std Resistor")
      (libsource (lib "ResistorCapacitorInductor") (part "SMD_Resistor"))
    )
    (comp (ref "R107")
      (value "10K")
      (footprint "RESC1608X04N_0603RES")
      (description "Std Resistor")
      (libsource (lib "ResistorCapacitorInductor") (part "SMD_Resistor"))
    )
    (comp (ref "R108")
      (value "10K")
      (footprint "RESC1608X04N_0603RES")
      (description "Std Resistor")
      (libsource (lib "ResistorCapacitorInductor") (part "SMD_Resistor"))
    )
    (comp (ref "R109")
      (value "47K")
      (footprint "RESC1608X04N_0603RES")
      (description "Std Resistor")
      (libsource (lib "ResistorCapacitorInductor") (part "SMD_Resistor"))
    )
    (comp (ref "R110")
      (value "0")
      (footprint "RESC6432X06N__2512RES")
      (description "Std Resistor")
      (libsource (lib "ResistorCapacitorInductor") (part "SMD_Resistor"))
    )
    (comp (ref "R111")
      (value "0")
      (footprint "RESC6432X06N__2512RES")
      (description "Std Resistor")
      (libsource (lib "ResistorCapacitorInductor") (part "SMD_Resistor"))
    )
    (comp (ref "R112")
      (value "4.7K")
      (footprint "RESC1608X04N_0603RES")
      (description "Std Resistor")
      (libsource (lib "ResistorCapacitorInductor") (part "SMD_Resistor"))
    )
    (comp (ref "R113")
      (value "1.8K")
      (footprint "RESC1608X04N_0603RES")
      (description "Std Resistor")
      (libsource (lib "ResistorCapacitorInductor") (part "SMD_Resistor"))
    )
    (comp (ref "R114")
      (value "0")
      (footprint "RESC6432X06N__2512RES")
      (description "Std Resistor")
      (libsource (lib "ResistorCapacitorInductor") (part "SMD_Resistor"))
    )
    (comp (ref "R116")
      (value "0")
      (footprint "RESC6432X06N__2512RES")
      (description "Std Resistor")
      (libsource (lib "ResistorCapacitorInductor") (part "SMD_Resistor"))
    )
    (comp (ref "R117")
      (value "10K")
      (footprint "RESC1608X04N_0603RES")
      (description "Std Resistor")
      (libsource (lib "ResistorCapacitorInductor") (part "SMD_Resistor"))
    )
    (comp (ref "R118")
      (value "27")
      (footprint "RESC1608X04N_0603RES")
      (description "Std Resistor")
      (libsource (lib "ResistorCapacitorInductor") (part "SMD_Resistor"))
    )
    (comp (ref "R119")
      (value "10K")
      (footprint "RESC1608X04N_0603RES")
      (description "Std Resistor")
      (libsource (lib "ResistorCapacitorInductor") (part "SMD_Resistor"))
    )
    (comp (ref "R120")
      (value "10K")
      (footprint "RESC1608X04N_0603RES")
      (description "Std Resistor")
      (libsource (lib "ResistorCapacitorInductor") (part "SMD_Resistor"))
    )
    (comp (ref "R121")
      (value "47K")
      (footprint "RESC1608X04N_0603RES")
      (description "Std Resistor")
      (libsource (lib "ResistorCapacitorInductor") (part "SMD_Resistor"))
    )
    (comp (ref "R122")
      (value "10K")
      (footprint "RESC1608X04N_0603RES")
      (description "Std Resistor")
      (libsource (lib "ResistorCapacitorInductor") (part "SMD_Resistor"))
    )
    (comp (ref "R123")
      (value "10K")
      (footprint "RESC1608X04N_0603RES")
      (description "Std Resistor")
      (libsource (lib "ResistorCapacitorInductor") (part "SMD_Resistor"))
    )
    (comp (ref "R124")
      (value "47K")
      (footprint "RESC1608X04N_0603RES")
      (description "Std Resistor")
      (libsource (lib "ResistorCapacitorInductor") (part "SMD_Resistor"))
    )
    (comp (ref "R125")
      (value "10K")
      (footprint "RESC1608X04N_0603RES")
      (description "Std Resistor")
      (libsource (lib "ResistorCapacitorInductor") (part "SMD_Resistor"))
    )
    (comp (ref "R126")
      (value "10K")
      (footprint "RESC1608X04N_0603RES")
      (description "Std Resistor")
      (libsource (lib "ResistorCapacitorInductor") (part "SMD_Resistor"))
    )
    (comp (ref "R127")
      (value "47K")
      (footprint "RESC1608X04N_0603RES")
      (description "Std Resistor")
      (libsource (lib "ResistorCapacitorInductor") (part "SMD_Resistor"))
    )
    (comp (ref "R128")
      (value "0")
      (footprint "RESC6432X06N__2512RES")
      (description "Std Resistor")
      (libsource (lib "ResistorCapacitorInductor") (part "SMD_Resistor"))
    )
    (comp (ref "R129")
      (value "0")
      (footprint "RESC6432X06N__2512RES")
      (description "Std Resistor")
      (libsource (lib "ResistorCapacitorInductor") (part "SMD_Resistor"))
    )
    (comp (ref "R130")
      (value "10K")
      (footprint "RESC1608X04N_0603RES")
      (description "Std Resistor")
      (libsource (lib "ResistorCapacitorInductor") (part "SMD_Resistor"))
    )
    (comp (ref "R131")
      (value "0")
      (footprint "RESC6432X06N__2512RES")
      (description "Std Resistor")
      (libsource (lib "ResistorCapacitorInductor") (part "SMD_Resistor"))
    )
    (comp (ref "R132")
      (value "0")
      (footprint "RESC6432X06N__2512RES")
      (description "Std Resistor")
      (libsource (lib "ResistorCapacitorInductor") (part "SMD_Resistor"))
    )
    (comp (ref "R133")
      (value "0")
      (footprint "RESC6432X06N__2512RES")
      (description "Std Resistor")
      (libsource (lib "ResistorCapacitorInductor") (part "SMD_Resistor"))
    )
    (comp (ref "R134")
      (value "1.2K")
      (footprint "RESC1608X04N_0603RES")
      (description "Std Resistor")
      (libsource (lib "ResistorCapacitorInductor") (part "SMD_Resistor"))
    )
    (comp (ref "R135")
      (value "47K")
      (footprint "RESC1608X04N_0603RES")
      (description "Std Resistor")
      (libsource (lib "ResistorCapacitorInductor") (part "SMD_Resistor"))
    )
    (comp (ref "R136")
      (value "0")
      (footprint "RESC6432X06N__2512RES")
      (description "Std Resistor")
      (libsource (lib "ResistorCapacitorInductor") (part "SMD_Resistor"))
    )
    (comp (ref "R137")
      (value "27")
      (footprint "RESC1608X04N_0603RES")
      (description "Std Resistor")
      (libsource (lib "ResistorCapacitorInductor") (part "SMD_Resistor"))
    )
    (comp (ref "R138")
      (value "10K")
      (footprint "RESC1608X04N_0603RES")
      (description "Std Resistor")
      (libsource (lib "ResistorCapacitorInductor") (part "SMD_Resistor"))
    )
    (comp (ref "R139")
      (value "10K")
      (footprint "RESC1608X04N_0603RES")
      (description "Std Resistor")
      (libsource (lib "ResistorCapacitorInductor") (part "SMD_Resistor"))
    )
    (comp (ref "R140")
      (value "10K")
      (footprint "RESC1608X04N_0603RES")
      (description "Std Resistor")
      (libsource (lib "ResistorCapacitorInductor") (part "SMD_Resistor"))
    )
    (comp (ref "R141")
      (value "47K")
      (footprint "RESC1608X04N_0603RES")
      (description "Std Resistor")
      (libsource (lib "ResistorCapacitorInductor") (part "SMD_Resistor"))
    )
    (comp (ref "R142")
      (value "10K")
      (footprint "RESC1608X04N_0603RES")
      (description "Std Resistor")
      (libsource (lib "ResistorCapacitorInductor") (part "SMD_Resistor"))
    )
    (comp (ref "R145")
      (value "10K")
      (footprint "RESC1608X04N_0603RES")
      (description "Std Resistor")
      (libsource (lib "ResistorCapacitorInductor") (part "SMD_Resistor"))
    )
    (comp (ref "R146")
      (value "47K")
      (footprint "RESC1608X04N_0603RES")
      (description "Std Resistor")
      (libsource (lib "ResistorCapacitorInductor") (part "SMD_Resistor"))
    )
    (comp (ref "R149")
      (value "4.7K")
      (footprint "RESC1608X04N_0603RES")
      (description "Std Resistor")
      (libsource (lib "ResistorCapacitorInductor") (part "SMD_Resistor"))
    )
    (comp (ref "R152")
      (value "27")
      (footprint "RESC1608X04N_0603RES")
      (description "Std Resistor")
      (libsource (lib "ResistorCapacitorInductor") (part "SMD_Resistor"))
    )
    (comp (ref "U2")
      (value "K7805MT_1000R4")
      (footprint "K7805MT_500R4")
      (libsource (lib "DCDC_Converter") (part "K78052MT_1000R4"))
    )
    (comp (ref "U4")
      (value "K7805MT_1000R4")
      (footprint "K7805MT_500R4")
      (libsource (lib "DCDC_Converter") (part "K78052MT_1000R4"))
    )
    (comp (ref "U5")
      (value "K7805MT_1000R4")
      (footprint "K7805MT_500R4")
      (libsource (lib "DCDC_Converter") (part "K78052MT_1000R4"))
    )
    (comp (ref "U6")
      (value "K7805MT_1000R4")
      (footprint "K7805MT_500R4")
      (libsource (lib "DCDC_Converter") (part "K78052MT_1000R4"))
    )
    (comp (ref "U7")
      (value "K7805MT_1000R4")
      (footprint "K7805MT_500R4")
      (libsource (lib "DCDC_Converter") (part "K78052MT_1000R4"))
    )
    (comp (ref "VBAT1")
      (value "Bolt_Connecter")
      (footprint "Bolt_Connecter")
      (libsource (lib "Connector") (part "Bolt_Connecter"))
    )
    (comp (ref "VBAT2")
      (value "Bolt_Connecter")
      (footprint "Bolt_Connecter")
      (libsource (lib "Connector") (part "Bolt_Connecter"))
    )
    (comp (ref "ZDB1")
      (value "SMAJ58CA")
      (footprint "SMA/DO214AC-BIPOLAR")
      (description "Bipolar Transient Voltage Supressor")
      (libsource (lib "Diodes") (part "TVS_Diode_Bipolar"))
    )
    (comp (ref "ZDB2")
      (value "SMAJ58CA")
      (footprint "SMA/DO214AC-BIPOLAR")
      (description "Bipolar Transient Voltage Supressor")
      (libsource (lib "Diodes") (part "TVS_Diode_Bipolar"))
    )
    (comp (ref "ZDB3")
      (value "SMAJ58CA")
      (footprint "SMA/DO214AC-BIPOLAR")
      (description "Bipolar Transient Voltage Supressor")
      (libsource (lib "Diodes") (part "TVS_Diode_Bipolar"))
    )
    (comp (ref "ZDB4")
      (value "SMAJ58CA")
      (footprint "SMA/DO214AC-BIPOLAR")
      (description "Bipolar Transient Voltage Supressor")
      (libsource (lib "Diodes") (part "TVS_Diode_Bipolar"))
    )
    (comp (ref "ZDB5")
      (value "SMAJ58CA")
      (footprint "SMA/DO214AC-BIPOLAR")
      (description "Bipolar Transient Voltage Supressor")
      (libsource (lib "Diodes") (part "TVS_Diode_Bipolar"))
    )
    (comp (ref "ZDB6")
      (value "SMAJ58CA")
      (footprint "SMA/DO214AC-BIPOLAR")
      (description "Bipolar Transient Voltage Supressor")
      (libsource (lib "Diodes") (part "TVS_Diode_Bipolar"))
    )
    (comp (ref "ZDB7")
      (value "SMAJ58CA")
      (footprint "SMA/DO214AC-BIPOLAR")
      (description "Bipolar Transient Voltage Supressor")
      (libsource (lib "Diodes") (part "TVS_Diode_Bipolar"))
    )
    (comp (ref "ZDB8")
      (value "SMAJ58CA")
      (footprint "SMA/DO214AC-BIPOLAR")
      (description "Bipolar Transient Voltage Supressor")
      (libsource (lib "Diodes") (part "TVS_Diode_Bipolar"))
    )
    (comp (ref "ZDB9")
      (value "SMAJ58CA")
      (footprint "SMA/DO214AC-BIPOLAR")
      (description "Bipolar Transient Voltage Supressor")
      (libsource (lib "Diodes") (part "TVS_Diode_Bipolar"))
    )
    (comp (ref "ZDB10")
      (value "SMAJ58CA")
      (footprint "SMA/DO214AC-BIPOLAR")
      (description "Bipolar Transient Voltage Supressor")
      (libsource (lib "Diodes") (part "TVS_Diode_Bipolar"))
    )
  )
  (nets
    (net (code "1") (name "/ACCU_PWR") (class "Default")
      (node (ref "C35") (pin "2") (pintype "passive"))
      (node (ref "IC5") (pin "13") (pinfunction "OUT3_13") (pintype "passive"))
      (node (ref "LOW1") (pin "16") (pinfunction "16_16") (pintype "passive"))
      (node (ref "R50") (pin "2") (pintype "passive"))
    )
    (net (code "2") (name "/ACCU_PWR_EN") (class "Default")
      (node (ref "CN3") (pin "36") (pinfunction "36_36") (pintype "passive"))
      (node (ref "R42") (pin "2") (pintype "passive"))
    )
    (net (code "3") (name "/ACCU_UBR") (class "Default")
      (node (ref "C73") (pin "2") (pintype "passive"))
      (node (ref "IC12") (pin "17") (pinfunction "OUT2_17") (pintype "passive"))
      (node (ref "LOW1") (pin "20") (pinfunction "20_20") (pintype "passive"))
      (node (ref "R127") (pin "2") (pintype "passive"))
    )
    (net (code "4") (name "/ACCU_UBR_EN") (class "Default")
      (node (ref "CN3") (pin "15") (pinfunction "15_15") (pintype "passive"))
      (node (ref "R125") (pin "2") (pintype "passive"))
    )
    (net (code "5") (name "/AIR+") (class "Default")
      (node (ref "HIGH") (pin "7") (pinfunction "7_7") (pintype "passive"))
      (node (ref "K2") (pin "1") (pinfunction "COIL_1_1") (pintype "passive"))
    )
    (net (code "6") (name "/BACKUP_PC10") (class "Default")
      (node (ref "CN4") (pin "11") (pinfunction "11_11") (pintype "passive+no_connect"))
    )
    (net (code "7") (name "/BACKUP_PC15") (class "Default")
      (node (ref "CN4") (pin "4") (pinfunction "4_4") (pintype "passive+no_connect"))
    )
    (net (code "8") (name "/BATTERY_1") (class "Default")
      (node (ref "CN4") (pin "18") (pinfunction "18_18") (pintype "passive"))
      (node (ref "FU2") (pin "1") (pintype "passive"))
      (node (ref "J7") (pin "+") (pinfunction "+_+") (pintype "passive"))
    )
    (net (code "9") (name "/BATTERY_2") (class "Default")
      (node (ref "CN4") (pin "17") (pinfunction "17_17") (pintype "passive"))
      (node (ref "J4") (pin "+") (pinfunction "+_+") (pintype "passive"))
      (node (ref "J7") (pin "-") (pinfunction "-_-") (pintype "passive"))
    )
    (net (code "10") (name "/BDU_PWR") (class "Default")
      (node (ref "C49") (pin "2") (pintype "passive"))
      (node (ref "IC7") (pin "13") (pinfunction "OUT3_13") (pintype "passive"))
      (node (ref "LOW1") (pin "17") (pinfunction "17_17") (pintype "passive"))
      (node (ref "R75") (pin "2") (pintype "passive"))
    )
    (net (code "11") (name "/BDU_PWR_EN") (class "Default")
      (node (ref "CN3") (pin "29") (pinfunction "29_29") (pintype "passive"))
      (node (ref "R69") (pin "2") (pintype "passive"))
    )
    (net (code "12") (name "/BSPD_PWR") (class "Default")
      (node (ref "C33") (pin "2") (pintype "passive"))
      (node (ref "IC5") (pin "17") (pinfunction "OUT2_17") (pintype "passive"))
      (node (ref "LOW1") (pin "6") (pinfunction "6_6") (pintype "passive"))
      (node (ref "R45") (pin "2") (pintype "passive"))
    )
    (net (code "13") (name "/BSPD_PWR_EN") (class "Default")
      (node (ref "CN3") (pin "37") (pinfunction "37_37") (pintype "passive"))
      (node (ref "R40") (pin "2") (pintype "passive"))
    )
    (net (code "14") (name "/BUZZER_CTRL") (class "Default")
      (node (ref "LOW2") (pin "10") (pinfunction "10_10") (pintype "passive+no_connect"))
    )
    (net (code "15") (name "/BUZZER_PWR") (class "Default")
      (node (ref "C58") (pin "2") (pintype "passive"))
      (node (ref "IC10") (pin "17") (pinfunction "OUT2_17") (pintype "passive"))
      (node (ref "LOW1") (pin "18") (pinfunction "18_18") (pintype "passive"))
      (node (ref "R96") (pin "2") (pintype "passive"))
    )
    (net (code "16") (name "/BUZZER_PWR_EN") (class "Default")
      (node (ref "CN3") (pin "22") (pinfunction "22_22") (pintype "passive"))
      (node (ref "R93") (pin "2") (pintype "passive"))
    )
    (net (code "17") (name "/CAN_H") (class "Default")
      (node (ref "CN4") (pin "7") (pinfunction "7_7") (pintype "passive"))
      (node (ref "LOW2") (pin "2") (pinfunction "2_2") (pintype "passive"))
    )
    (net (code "18") (name "/CAN_L") (class "Default")
      (node (ref "CN4") (pin "8") (pinfunction "8_8") (pintype "passive"))
      (node (ref "LOW2") (pin "1") (pinfunction "1_1") (pintype "passive"))
    )
    (net (code "19") (name "/DCDC_CTRL") (class "Default")
      (node (ref "HIGH") (pin "6") (pinfunction "6_6") (pintype "passive"))
      (node (ref "K1") (pin "5") (pinfunction "COIL_1_5") (pintype "passive"))
    )
    (net (code "20") (name "/DCDC_IN") (class "Default")
      (node (ref "DCDC_IN") (pin "1") (pinfunction "1_1") (pintype "passive"))
      (node (ref "DCDC_IN") (pin "2") (pinfunction "2_2") (pintype "passive"))
      (node (ref "DCDC_IN") (pin "3") (pinfunction "3_3") (pintype "passive"))
      (node (ref "DCDC_IN") (pin "4") (pinfunction "4_4") (pintype "passive"))
      (node (ref "FU1") (pin "1") (pintype "passive"))
    )
    (net (code "21") (name "/DRS_CTRL") (class "Default")
      (node (ref "CN4") (pin "10") (pinfunction "10_10") (pintype "passive"))
      (node (ref "LOW2") (pin "3") (pinfunction "3_3") (pintype "passive"))
    )
    (net (code "22") (name "/DRS_PWR_8V") (class "Default")
      (node (ref "C1") (pin "1") (pinfunction "+_1") (pintype "passive"))
      (node (ref "HIGH") (pin "17") (pinfunction "17_17") (pintype "passive"))
      (node (ref "L1") (pin "2") (pinfunction "2_2") (pintype "passive"))
      (node (ref "R2") (pin "2") (pintype "passive"))
    )
    (net (code "23") (name "/DRS_PWR_8V_EN") (class "Default")
      (node (ref "CN4") (pin "40") (pinfunction "40_40") (pintype "passive"))
      (node (ref "R140") (pin "2") (pintype "passive"))
    )
    (net (code "24") (name "/DRS_PWR_8V_a") (class "Default")
      (node (ref "C83") (pin "2") (pintype "passive"))
      (node (ref "C84") (pin "2") (pintype "passive"))
      (node (ref "IC13") (pin "12") (pinfunction "OUT0_1_12") (pintype "passive"))
      (node (ref "IC13") (pin "13") (pinfunction "OUT0_2_13") (pintype "passive"))
      (node (ref "IC13") (pin "14") (pinfunction "OUT0_3_14") (pintype "passive"))
      (node (ref "IC14") (pin "7") (pinfunction "VIN_7") (pintype "passive"))
      (node (ref "R141") (pin "2") (pintype "passive"))
    )
    (net (code "25") (name "/DSBD_PWR") (class "Default")
      (node (ref "C25") (pin "2") (pintype "passive"))
      (node (ref "IC2") (pin "13") (pinfunction "OUT3_13") (pintype "passive"))
      (node (ref "LOW1") (pin "5") (pinfunction "5_5") (pintype "passive"))
      (node (ref "R25") (pin "2") (pintype "passive"))
    )
    (net (code "26") (name "/DSBD_PWR_EN") (class "Default")
      (node (ref "CN3") (pin "9") (pinfunction "9_9") (pintype "passive"))
      (node (ref "R19") (pin "2") (pintype "passive"))
    )
    (net (code "27") (name "/ENERGE_METER_PWR") (class "Default")
      (node (ref "C72") (pin "2") (pintype "passive"))
      (node (ref "IC12") (pin "20") (pinfunction "OUT1_20") (pintype "passive"))
      (node (ref "LOW1") (pin "9") (pinfunction "9_9") (pintype "passive"))
      (node (ref "R124") (pin "2") (pintype "passive"))
    )
    (net (code "28") (name "/ENERGE_METER_PWR_EN") (class "Default")
      (node (ref "CN3") (pin "12") (pinfunction "12_12") (pintype "passive"))
      (node (ref "R123") (pin "2") (pintype "passive"))
    )
    (net (code "29") (name "/FAN1_PWR") (class "Default")
      (node (ref "C52") (pin "2") (pintype "passive"))
      (node (ref "HIGH") (pin "14") (pinfunction "14_14") (pintype "passive"))
      (node (ref "IC9") (pin "10") (pinfunction "OUT1_3_10") (pintype "passive"))
      (node (ref "IC9") (pin "8") (pinfunction "OUT1_1_8") (pintype "passive"))
      (node (ref "IC9") (pin "9") (pinfunction "OUT1_2_9") (pintype "passive"))
      (node (ref "R80") (pin "2") (pintype "passive"))
    )
    (net (code "30") (name "/FAN1_PWR_EN") (class "Default")
      (node (ref "CN4") (pin "29") (pinfunction "29_29") (pintype "passive"))
      (node (ref "R78") (pin "2") (pintype "passive"))
    )
    (net (code "31") (name "/FAN2_PWR") (class "Default")
      (node (ref "C62") (pin "2") (pintype "passive"))
      (node (ref "HIGH") (pin "15") (pinfunction "15_15") (pintype "passive"))
      (node (ref "IC11") (pin "10") (pinfunction "OUT1_3_10") (pintype "passive"))
      (node (ref "IC11") (pin "8") (pinfunction "OUT1_1_8") (pintype "passive"))
      (node (ref "IC11") (pin "9") (pinfunction "OUT1_2_9") (pintype "passive"))
      (node (ref "R109") (pin "2") (pintype "passive"))
    )
    (net (code "32") (name "/FAN2_PWR_EN") (class "Default")
      (node (ref "CN4") (pin "33") (pinfunction "33_33") (pintype "passive"))
      (node (ref "R107") (pin "2") (pintype "passive"))
    )
    (net (code "33") (name "/FAN3_PWR") (class "Default")
      (node (ref "C61") (pin "2") (pintype "passive"))
      (node (ref "HIGH") (pin "16") (pinfunction "16_16") (pintype "passive"))
      (node (ref "IC11") (pin "12") (pinfunction "OUT0_1_12") (pintype "passive"))
      (node (ref "IC11") (pin "13") (pinfunction "OUT0_2_13") (pintype "passive"))
      (node (ref "IC11") (pin "14") (pinfunction "OUT0_3_14") (pintype "passive"))
      (node (ref "R106") (pin "2") (pintype "passive"))
    )
    (net (code "34") (name "/FAN3_PWR_EN") (class "Default")
      (node (ref "CN4") (pin "36") (pinfunction "36_36") (pintype "passive"))
      (node (ref "R105") (pin "2") (pintype "passive"))
    )
    (net (code "35") (name "/FIREON_PWR") (class "Default")
      (node (ref "C17") (pin "2") (pintype "passive"))
      (node (ref "IC2") (pin "17") (pinfunction "OUT2_17") (pintype "passive"))
      (node (ref "LOW1") (pin "4") (pinfunction "4_4") (pintype "passive"))
      (node (ref "R21") (pin "2") (pintype "passive"))
    )
    (net (code "36") (name "/FIREON_PWR_EN") (class "Default")
      (node (ref "CN3") (pin "8") (pinfunction "8_8") (pintype "passive"))
      (node (ref "R17") (pin "2") (pintype "passive"))
    )
    (net (code "37") (name "/GLVMS-") (class "Default")
      (node (ref "C29") (pin "1") (pintype "passive"))
      (node (ref "C54") (pin "1") (pintype "passive"))
      (node (ref "C6") (pin "1") (pintype "passive"))
      (node (ref "C63") (pin "1") (pintype "passive"))
      (node (ref "C7") (pin "1") (pintype "passive"))
      (node (ref "CN4") (pin "3") (pinfunction "3_3") (pintype "passive"))
      (node (ref "GLVMS-") (pin "1") (pinfunction "1_1") (pintype "passive"))
      (node (ref "GLVMS-") (pin "2") (pinfunction "2_2") (pintype "passive"))
      (node (ref "GLVMS-") (pin "3") (pinfunction "3_3") (pintype "passive"))
      (node (ref "GLVMS-") (pin "4") (pinfunction "4_4") (pintype "passive"))
      (node (ref "IC10") (pin "25") (pinfunction "VS_25") (pintype "passive"))
      (node (ref "IC12") (pin "25") (pinfunction "VS_25") (pintype "passive"))
      (node (ref "IC2") (pin "25") (pinfunction "VS_25") (pintype "passive"))
      (node (ref "IC3") (pin "15") (pinfunction "VS_15") (pintype "passive"))
      (node (ref "IC6") (pin "15") (pinfunction "VS_15") (pintype "passive"))
      (node (ref "K1") (pin "6") (pinfunction "COIL_2_6") (pintype "passive"))
      (node (ref "R10") (pin "1") (pintype "passive"))
      (node (ref "R30") (pin "1") (pintype "passive"))
      (node (ref "R6") (pin "1") (pintype "passive"))
      (node (ref "ZDB1") (pin "2") (pintype "passive"))
      (node (ref "ZDB2") (pin "2") (pintype "passive"))
      (node (ref "ZDB4") (pin "2") (pintype "passive"))
      (node (ref "ZDB7") (pin "2") (pintype "passive"))
      (node (ref "ZDB9") (pin "2") (pintype "passive"))
    )
    (net (code "38") (name "/GLVMS-1") (class "Default")
      (node (ref "C42") (pin "1") (pintype "passive"))
      (node (ref "IC7") (pin "25") (pinfunction "VS_25") (pintype "passive"))
      (node (ref "R28") (pin "1") (pintype "passive"))
      (node (ref "R30") (pin "2") (pintype "passive"))
      (node (ref "ZDB5") (pin "2") (pintype "passive"))
    )
    (net (code "39") (name "/GLVMS-2") (class "Default")
      (node (ref "C28") (pin "1") (pintype "passive"))
      (node (ref "IC5") (pin "25") (pinfunction "VS_25") (pintype "passive"))
      (node (ref "R28") (pin "2") (pintype "passive"))
      (node (ref "ZDB3") (pin "2") (pintype "passive"))
    )
    (net (code "40") (name "/GLVMS-3") (class "Default")
      (node (ref "C57") (pin "1") (pintype "passive"))
      (node (ref "IC11") (pin "15") (pinfunction "VS_15") (pintype "passive"))
      (node (ref "R6") (pin "2") (pintype "passive"))
      (node (ref "ZDB8") (pin "2") (pintype "passive"))
    )
    (net (code "41") (name "/GLVMS-4") (class "Default")
      (node (ref "C44") (pin "1") (pintype "passive"))
      (node (ref "IC9") (pin "15") (pinfunction "VS_15") (pintype "passive"))
      (node (ref "R1") (pin "1") (pintype "passive"))
      (node (ref "R10") (pin "2") (pintype "passive"))
      (node (ref "ZDB6") (pin "2") (pintype "passive"))
    )
    (net (code "42") (name "/GLVMS-5") (class "Default")
      (node (ref "C74") (pin "1") (pintype "passive"))
      (node (ref "IC13") (pin "15") (pinfunction "VS_15") (pintype "passive"))
      (node (ref "R1") (pin "2") (pintype "passive"))
      (node (ref "R32") (pin "2") (pintype "passive"))
      (node (ref "ZDB10") (pin "2") (pintype "passive"))
    )
    (net (code "43") (name "/H1_24V_Backup") (class "Default")
      (node (ref "C32") (pin "2") (pintype "passive"))
      (node (ref "HIGH") (pin "4") (pinfunction "4_4") (pintype "passive"))
      (node (ref "IC6") (pin "12") (pinfunction "OUT0_1_12") (pintype "passive"))
      (node (ref "IC6") (pin "13") (pinfunction "OUT0_2_13") (pintype "passive"))
      (node (ref "IC6") (pin "14") (pinfunction "OUT0_3_14") (pintype "passive"))
      (node (ref "R43") (pin "2") (pintype "passive"))
    )
    (net (code "44") (name "/H1_24V_Backup_EN") (class "Default")
      (node (ref "CN4") (pin "28") (pinfunction "28_28") (pintype "passive"))
      (node (ref "R41") (pin "2") (pintype "passive"))
    )
    (net (code "45") (name "/H1_current_IN10") (class "Default")
      (node (ref "C23") (pin "2") (pintype "passive"))
      (node (ref "CN4") (pin "23") (pinfunction "23_23") (pintype "passive"))
      (node (ref "R18") (pin "2") (pintype "passive"))
    )
    (net (code "46") (name "/H1_select") (class "Default")
      (node (ref "CN4") (pin "22") (pinfunction "22_22") (pintype "passive"))
      (node (ref "R8") (pin "2") (pintype "passive"))
    )
    (net (code "47") (name "/H2_24V_Backup") (class "Default")
      (node (ref "C50") (pin "2") (pintype "passive"))
      (node (ref "HIGH") (pin "5") (pinfunction "5_5") (pintype "passive"))
      (node (ref "IC9") (pin "12") (pinfunction "OUT0_1_12") (pintype "passive"))
      (node (ref "IC9") (pin "13") (pinfunction "OUT0_2_13") (pintype "passive"))
      (node (ref "IC9") (pin "14") (pinfunction "OUT0_3_14") (pintype "passive"))
      (node (ref "R76") (pin "2") (pintype "passive"))
    )
    (net (code "48") (name "/H2_24V_Backup_EN") (class "Default")
      (node (ref "CN4") (pin "32") (pinfunction "32_32") (pintype "passive"))
      (node (ref "R73") (pin "2") (pintype "passive"))
    )
    (net (code "49") (name "/H2_current_IN11") (class "Default")
      (node (ref "C37") (pin "2") (pintype "passive"))
      (node (ref "CN4") (pin "27") (pinfunction "27_27") (pintype "passive"))
      (node (ref "R47") (pin "2") (pintype "passive"))
    )
    (net (code "50") (name "/H2_select") (class "Default")
      (node (ref "CN4") (pin "26") (pinfunction "26_26") (pintype "passive"))
      (node (ref "R38") (pin "2") (pintype "passive"))
    )
    (net (code "51") (name "/H3_24V_Backup") (class "Default")
      (node (ref "C85") (pin "2") (pintype "passive"))
      (node (ref "HIGH") (pin "18") (pinfunction "18_18") (pintype "passive"))
      (node (ref "IC13") (pin "10") (pinfunction "OUT1_3_10") (pintype "passive"))
      (node (ref "IC13") (pin "8") (pinfunction "OUT1_1_8") (pintype "passive"))
      (node (ref "IC13") (pin "9") (pinfunction "OUT1_2_9") (pintype "passive"))
      (node (ref "R146") (pin "2") (pintype "passive"))
    )
    (net (code "52") (name "/H3_24V_Backup_EN") (class "Default")
      (node (ref "CN4") (pin "37") (pinfunction "37_37") (pintype "passive"))
      (node (ref "R142") (pin "2") (pintype "passive"))
    )
    (net (code "53") (name "/H3_current_IN12") (class "Default")
      (node (ref "C53") (pin "2") (pintype "passive"))
      (node (ref "CN4") (pin "31") (pinfunction "31_31") (pintype "passive"))
      (node (ref "R79") (pin "2") (pintype "passive"))
    )
    (net (code "54") (name "/H3_select") (class "Default")
      (node (ref "CN4") (pin "30") (pinfunction "30_30") (pintype "passive"))
      (node (ref "R71") (pin "2") (pintype "passive"))
    )
    (net (code "55") (name "/H4_current_IN13") (class "Default")
      (node (ref "C64") (pin "2") (pintype "passive"))
      (node (ref "CN4") (pin "35") (pinfunction "35_35") (pintype "passive"))
      (node (ref "R108") (pin "2") (pintype "passive"))
    )
    (net (code "56") (name "/H4_select") (class "Default")
      (node (ref "CN4") (pin "34") (pinfunction "34_34") (pintype "passive"))
      (node (ref "R104") (pin "2") (pintype "passive"))
    )
    (net (code "57") (name "/H5_current_IN1") (class "Default")
      (node (ref "C90") (pin "2") (pintype "passive"))
      (node (ref "CN4") (pin "39") (pinfunction "39_39") (pintype "passive"))
      (node (ref "R145") (pin "2") (pintype "passive"))
    )
    (net (code "58") (name "/H5_select") (class "Default")
      (node (ref "CN4") (pin "38") (pinfunction "38_38") (pintype "passive"))
      (node (ref "R139") (pin "2") (pintype "passive"))
    )
    (net (code "59") (name "/IL+_PWR") (class "Default")
      (node (ref "C14") (pin "2") (pintype "passive"))
      (node (ref "HIGH") (pin "12") (pinfunction "12_12") (pintype "passive"))
      (node (ref "IC3") (pin "12") (pinfunction "OUT0_1_12") (pintype "passive"))
      (node (ref "IC3") (pin "13") (pinfunction "OUT0_2_13") (pintype "passive"))
      (node (ref "IC3") (pin "14") (pinfunction "OUT0_3_14") (pintype "passive"))
      (node (ref "R14") (pin "2") (pintype "passive"))
    )
    (net (code "60") (name "/IL+_PWR_EN") (class "Default")
      (node (ref "CN4") (pin "21") (pinfunction "21_21") (pintype "passive"))
      (node (ref "R16") (pin "2") (pintype "passive"))
    )
    (net (code "61") (name "/L1_5V_Backup") (class "Default")
      (node (ref "LOW1") (pin "1") (pinfunction "1_1") (pintype "passive"))
      (node (ref "R128") (pin "2") (pintype "passive"))
      (node (ref "R129") (pin "2") (pintype "passive"))
    )
    (net (code "62") (name "/L1_5V_Backup_EN") (class "Default")
      (node (ref "CN3") (pin "4") (pinfunction "4_4") (pintype "passive"))
      (node (ref "R11") (pin "2") (pintype "passive"))
    )
    (net (code "63") (name "/L1_5V_Backup_a") (class "Default")
      (node (ref "C12") (pin "2") (pintype "passive"))
      (node (ref "C78") (pin "2") (pintype "passive"))
      (node (ref "IC2") (pin "24") (pinfunction "OUT0_24") (pintype "passive"))
      (node (ref "R128") (pin "1") (pintype "passive"))
      (node (ref "R9") (pin "2") (pintype "passive"))
      (node (ref "U5") (pin "1") (pinfunction "+Vin_1") (pintype "passive"))
      (node (ref "U5") (pin "6") (pinfunction "Ctrl_6") (pintype "passive"))
    )
    (net (code "64") (name "/L1_24V_Backup") (class "Default")
      (node (ref "C31") (pin "2") (pintype "passive"))
      (node (ref "IC5") (pin "20") (pinfunction "OUT1_20") (pintype "passive"))
      (node (ref "LOW1") (pin "15") (pinfunction "15_15") (pintype "passive"))
      (node (ref "R39") (pin "2") (pintype "passive"))
    )
    (net (code "65") (name "/L1_24V_Backup_EN") (class "Default")
      (node (ref "CN3") (pin "40") (pinfunction "40_40") (pintype "passive"))
      (node (ref "R37") (pin "2") (pintype "passive"))
    )
    (net (code "66") (name "/L1_current_IN3") (class "Default")
      (node (ref "C26") (pin "2") (pintype "passive"))
      (node (ref "CN3") (pin "6") (pinfunction "6_6") (pintype "passive"))
      (node (ref "R22") (pin "2") (pintype "passive"))
    )
    (net (code "67") (name "/L1_select0") (class "Default")
      (node (ref "CN3") (pin "7") (pinfunction "7_7") (pintype "passive"))
      (node (ref "R4") (pin "2") (pintype "passive"))
    )
    (net (code "68") (name "/L1_select1") (class "Default")
      (node (ref "CN3") (pin "10") (pinfunction "10_10") (pintype "passive"))
      (node (ref "R7") (pin "2") (pintype "passive"))
    )
    (net (code "69") (name "/L2_5V_Backup") (class "Default")
      (node (ref "LOW1") (pin "12") (pinfunction "12_12") (pintype "passive"))
      (node (ref "R131") (pin "2") (pintype "passive"))
      (node (ref "R132") (pin "2") (pintype "passive"))
    )
    (net (code "70") (name "/L2_5V_Backup_EN") (class "Default")
      (node (ref "CN3") (pin "34") (pinfunction "34_34") (pintype "passive"))
      (node (ref "R63") (pin "2") (pintype "passive"))
    )
    (net (code "71") (name "/L2_5V_Backupa_a") (class "Default")
      (node (ref "C45") (pin "2") (pintype "passive"))
      (node (ref "C81") (pin "2") (pintype "passive"))
      (node (ref "IC7") (pin "24") (pinfunction "OUT0_24") (pintype "passive"))
      (node (ref "R132") (pin "1") (pintype "passive"))
      (node (ref "R61") (pin "2") (pintype "passive"))
      (node (ref "U6") (pin "1") (pinfunction "+Vin_1") (pintype "passive"))
      (node (ref "U6") (pin "6") (pinfunction "Ctrl_6") (pintype "passive"))
    )
    (net (code "72") (name "/L2_24V_Backup") (class "Default")
      (node (ref "C13") (pin "2") (pintype "passive"))
      (node (ref "IC2") (pin "20") (pinfunction "OUT1_20") (pintype "passive"))
      (node (ref "LOW1") (pin "14") (pinfunction "14_14") (pintype "passive"))
      (node (ref "R15") (pin "2") (pintype "passive"))
    )
    (net (code "73") (name "/L2_24V_Backup_EN") (class "Default")
      (node (ref "CN3") (pin "5") (pinfunction "5_5") (pintype "passive"))
      (node (ref "R13") (pin "2") (pintype "passive"))
    )
    (net (code "74") (name "/L2_current_IN4") (class "Default")
      (node (ref "C36") (pin "2") (pintype "passive"))
      (node (ref "CN3") (pin "39") (pinfunction "39_39") (pintype "passive"))
      (node (ref "R46") (pin "2") (pintype "passive"))
    )
    (net (code "75") (name "/L2_select0") (class "Default")
      (node (ref "CN3") (pin "38") (pinfunction "38_38") (pintype "passive"))
      (node (ref "R31") (pin "2") (pintype "passive"))
    )
    (net (code "76") (name "/L2_select1") (class "Default")
      (node (ref "CN3") (pin "35") (pinfunction "35_35") (pintype "passive"))
      (node (ref "R33") (pin "2") (pintype "passive"))
    )
    (net (code "77") (name "/L3_5V_Backup") (class "Default")
      (node (ref "LOW1") (pin "11") (pinfunction "11_11") (pintype "passive"))
      (node (ref "R114") (pin "2") (pintype "passive"))
      (node (ref "R116") (pin "2") (pintype "passive"))
    )
    (net (code "78") (name "/L3_5V_Backup_EN") (class "Default")
      (node (ref "CN3") (pin "1") (pinfunction "1_1") (pintype "passive"))
      (node (ref "R35") (pin "2") (pintype "passive"))
    )
    (net (code "79") (name "/L3_5V_Backup_a") (class "Default")
      (node (ref "C30") (pin "2") (pintype "passive"))
      (node (ref "C75") (pin "2") (pintype "passive"))
      (node (ref "IC5") (pin "24") (pinfunction "OUT0_24") (pintype "passive"))
      (node (ref "R116") (pin "1") (pintype "passive"))
      (node (ref "R34") (pin "2") (pintype "passive"))
      (node (ref "U4") (pin "1") (pinfunction "+Vin_1") (pintype "passive"))
      (node (ref "U4") (pin "6") (pinfunction "Ctrl_6") (pintype "passive"))
    )
    (net (code "80") (name "/L3_current_IN5") (class "Default")
      (node (ref "C51") (pin "2") (pintype "passive"))
      (node (ref "CN3") (pin "32") (pinfunction "32_32") (pintype "passive"))
      (node (ref "R72") (pin "2") (pintype "passive"))
    )
    (net (code "81") (name "/L3_select0") (class "Default")
      (node (ref "CN3") (pin "31") (pinfunction "31_31") (pintype "passive"))
      (node (ref "R59") (pin "2") (pintype "passive"))
    )
    (net (code "82") (name "/L3_select1") (class "Default")
      (node (ref "CN3") (pin "28") (pinfunction "28_28") (pintype "passive"))
      (node (ref "R60") (pin "2") (pintype "passive"))
    )
    (net (code "83") (name "/L4_5V_Backup") (class "Default")
      (node (ref "LOW2") (pin "13") (pinfunction "13_13") (pintype "passive"))
      (node (ref "LOW2") (pin "14") (pinfunction "14_14") (pintype "passive"))
      (node (ref "LOW2") (pin "15") (pinfunction "15_15") (pintype "passive"))
      (node (ref "LOW2") (pin "16") (pinfunction "16_16") (pintype "passive"))
      (node (ref "LOW2") (pin "17") (pinfunction "17_17") (pintype "passive"))
      (node (ref "LOW2") (pin "18") (pinfunction "18_18") (pintype "passive"))
      (node (ref "R133") (pin "2") (pintype "passive"))
      (node (ref "R136") (pin "2") (pintype "passive"))
    )
    (net (code "84") (name "/L4_5V_Backup_EN") (class "Default")
      (node (ref "CN3") (pin "11") (pinfunction "11_11") (pintype "passive"))
      (node (ref "R122") (pin "2") (pintype "passive"))
    )
    (net (code "85") (name "/L4_5V_Backup_a") (class "Default")
      (node (ref "C71") (pin "2") (pintype "passive"))
      (node (ref "C86") (pin "2") (pintype "passive"))
      (node (ref "IC12") (pin "24") (pinfunction "OUT0_24") (pintype "passive"))
      (node (ref "R121") (pin "2") (pintype "passive"))
      (node (ref "R136") (pin "1") (pintype "passive"))
      (node (ref "U7") (pin "1") (pinfunction "+Vin_1") (pintype "passive"))
      (node (ref "U7") (pin "6") (pinfunction "Ctrl_6") (pintype "passive"))
    )
    (net (code "86") (name "/L4_current_IN6") (class "Default")
      (node (ref "C60") (pin "2") (pintype "passive"))
      (node (ref "CN3") (pin "24") (pinfunction "24_24") (pintype "passive"))
      (node (ref "R98") (pin "2") (pintype "passive"))
    )
    (net (code "87") (name "/L4_select0") (class "Default")
      (node (ref "CN3") (pin "23") (pinfunction "23_23") (pintype "passive"))
      (node (ref "R87") (pin "2") (pintype "passive"))
    )
    (net (code "88") (name "/L4_select1") (class "Default")
      (node (ref "CN3") (pin "20") (pinfunction "20_20") (pintype "passive"))
      (node (ref "R88") (pin "2") (pintype "passive"))
    )
    (net (code "89") (name "/L5_current_IN7") (class "Default")
      (node (ref "C80") (pin "2") (pintype "passive"))
      (node (ref "CN3") (pin "13") (pinfunction "13_13") (pintype "passive"))
      (node (ref "R130") (pin "2") (pintype "passive"))
    )
    (net (code "90") (name "/L5_select0") (class "Default")
      (node (ref "CN3") (pin "14") (pinfunction "14_14") (pintype "passive"))
      (node (ref "R119") (pin "2") (pintype "passive"))
    )
    (net (code "91") (name "/L5_select1") (class "Default")
      (node (ref "CN3") (pin "17") (pinfunction "17_17") (pintype "passive"))
      (node (ref "R120") (pin "2") (pintype "passive"))
    )
    (net (code "92") (name "/LOGGER_PWR") (class "Default")
      (node (ref "C59") (pin "2") (pintype "passive"))
      (node (ref "IC10") (pin "13") (pinfunction "OUT3_13") (pintype "passive"))
      (node (ref "LOW1") (pin "19") (pinfunction "19_19") (pintype "passive"))
      (node (ref "R101") (pin "2") (pintype "passive"))
    )
    (net (code "93") (name "/LOGGER_PWR_EN") (class "Default")
      (node (ref "CN3") (pin "21") (pinfunction "21_21") (pintype "passive"))
      (node (ref "R95") (pin "2") (pintype "passive"))
    )
    (net (code "94") (name "/MCU_UBR") (class "Default")
      (node (ref "C77") (pin "2") (pintype "passive"))
      (node (ref "IC12") (pin "13") (pinfunction "OUT3_13") (pintype "passive"))
      (node (ref "LOW1") (pin "10") (pinfunction "10_10") (pintype "passive"))
      (node (ref "R135") (pin "2") (pintype "passive"))
    )
    (net (code "95") (name "/MCU_UBR_EN") (class "Default")
      (node (ref "CN3") (pin "16") (pinfunction "16_16") (pintype "passive"))
      (node (ref "R126") (pin "2") (pintype "passive"))
    )
    (net (code "96") (name "/PUMP_CTRL") (class "Default")
      (node (ref "LOW2") (pin "11") (pinfunction "11_11") (pintype "passive+no_connect"))
    )
    (net (code "97") (name "/PUMP_PWR") (class "Default")
      (node (ref "C34") (pin "2") (pintype "passive"))
      (node (ref "HIGH") (pin "13") (pinfunction "13_13") (pintype "passive"))
      (node (ref "IC6") (pin "10") (pinfunction "OUT1_3_10") (pintype "passive"))
      (node (ref "IC6") (pin "8") (pinfunction "OUT1_1_8") (pintype "passive"))
      (node (ref "IC6") (pin "9") (pinfunction "OUT1_2_9") (pintype "passive"))
      (node (ref "R48") (pin "2") (pintype "passive"))
    )
    (net (code "98") (name "/PUMP_PWR_EN") (class "Default")
      (node (ref "CN4") (pin "25") (pinfunction "25_25") (pintype "passive"))
      (node (ref "R44") (pin "2") (pintype "passive"))
    )
    (net (code "99") (name "/TAILLIGHT_PWR") (class "Default")
      (node (ref "LOW1") (pin "2") (pinfunction "2_2") (pintype "passive"))
      (node (ref "R110") (pin "2") (pintype "passive"))
      (node (ref "R111") (pin "2") (pintype "passive"))
    )
    (net (code "100") (name "/TAILLIGHT_PWR_EN") (class "Default")
      (node (ref "CN3") (pin "26") (pinfunction "26_26") (pintype "passive"))
      (node (ref "R90") (pin "2") (pintype "passive"))
    )
    (net (code "101") (name "/TAILLIGHT_PWR_a") (class "Default")
      (node (ref "C55") (pin "2") (pintype "passive"))
      (node (ref "C67") (pin "2") (pintype "passive"))
      (node (ref "IC10") (pin "24") (pinfunction "OUT0_24") (pintype "passive"))
      (node (ref "R110") (pin "1") (pintype "passive"))
      (node (ref "R89") (pin "2") (pintype "passive"))
      (node (ref "U2") (pin "1") (pinfunction "+Vin_1") (pintype "passive"))
      (node (ref "U2") (pin "6") (pinfunction "Ctrl_6") (pintype "passive"))
    )
    (net (code "102") (name "/TSALR_PWR") (class "Default")
      (node (ref "C56") (pin "2") (pintype "passive"))
      (node (ref "IC10") (pin "20") (pinfunction "OUT1_20") (pintype "passive"))
      (node (ref "LOW1") (pin "8") (pinfunction "8_8") (pintype "passive"))
      (node (ref "R92") (pin "2") (pintype "passive"))
    )
    (net (code "103") (name "/TSALR_PWR_EN") (class "Default")
      (node (ref "CN3") (pin "25") (pinfunction "25_25") (pintype "passive"))
      (node (ref "R91") (pin "2") (pintype "passive"))
    )
    (net (code "104") (name "/Temperature_PWR") (class "Default")
      (node (ref "C47") (pin "2") (pintype "passive"))
      (node (ref "IC7") (pin "20") (pinfunction "OUT1_20") (pintype "passive"))
      (node (ref "LOW2") (pin "4") (pinfunction "4_4") (pintype "passive"))
      (node (ref "LOW2") (pin "5") (pinfunction "5_5") (pintype "passive"))
      (node (ref "LOW2") (pin "6") (pinfunction "6_6") (pintype "passive"))
      (node (ref "LOW2") (pin "7") (pinfunction "7_7") (pintype "passive"))
      (node (ref "LOW2") (pin "8") (pinfunction "8_8") (pintype "passive"))
      (node (ref "LOW2") (pin "9") (pinfunction "9_9") (pintype "passive"))
      (node (ref "R66") (pin "2") (pintype "passive"))
    )
    (net (code "105") (name "/Temperature_PWR_EN") (class "Default")
      (node (ref "CN3") (pin "33") (pinfunction "33_33") (pintype "passive"))
      (node (ref "R65") (pin "2") (pintype "passive"))
    )
    (net (code "106") (name "/VCU_PWR") (class "Default")
      (node (ref "C48") (pin "2") (pintype "passive"))
      (node (ref "IC7") (pin "17") (pinfunction "OUT2_17") (pintype "passive"))
      (node (ref "LOW1") (pin "7") (pinfunction "7_7") (pintype "passive"))
      (node (ref "R70") (pin "2") (pintype "passive"))
    )
    (net (code "107") (name "/VCU_PWR_EN") (class "Default")
      (node (ref "CN3") (pin "30") (pinfunction "30_30") (pintype "passive"))
      (node (ref "R67") (pin "2") (pintype "passive"))
    )
    (net (code "108") (name "/VCU_UBR") (class "Default")
      (node (ref "C22") (pin "2") (pintype "passive"))
      (node (ref "HIGH") (pin "3") (pinfunction "3_3") (pintype "passive"))
      (node (ref "IC3") (pin "10") (pinfunction "OUT1_3_10") (pintype "passive"))
      (node (ref "IC3") (pin "8") (pinfunction "OUT1_1_8") (pintype "passive"))
      (node (ref "IC3") (pin "9") (pinfunction "OUT1_2_9") (pintype "passive"))
      (node (ref "R20") (pin "2") (pintype "passive"))
    )
    (net (code "109") (name "/VCU_UBR_CTRL") (class "Default")
      (node (ref "LOW2") (pin "12") (pinfunction "12_12") (pintype "passive+no_connect"))
    )
    (net (code "110") (name "/VCU_UBR_EN") (class "Default")
      (node (ref "CN4") (pin "24") (pinfunction "24_24") (pintype "passive"))
      (node (ref "R12") (pin "2") (pintype "passive"))
    )
    (net (code "111") (name "/active_switch_IL+") (class "Default")
      (node (ref "HIGH") (pin "8") (pinfunction "8_8") (pintype "passive"))
      (node (ref "K2") (pin "4") (pinfunction "COM_4") (pintype "passive"))
    )
    (net (code "112") (name "/active_switch_IL-") (class "Default")
      (node (ref "HIGH") (pin "9") (pinfunction "9_9") (pintype "passive"))
      (node (ref "K2") (pin "3") (pinfunction "NO_3") (pintype "passive"))
    )
    (net (code "113") (name "5V") (class "Default")
      (node (ref "CN4") (pin "13") (pinfunction "13_13") (pintype "passive"))
      (node (ref "CN4") (pin "14") (pinfunction "14_14") (pintype "passive"))
      (node (ref "R102") (pin "2") (pintype "passive"))
      (node (ref "R117") (pin "2") (pintype "passive"))
      (node (ref "R138") (pin "2") (pintype "passive"))
      (node (ref "R29") (pin "2") (pintype "passive"))
      (node (ref "R3") (pin "2") (pintype "passive"))
      (node (ref "R36") (pin "2") (pintype "passive"))
      (node (ref "R5") (pin "2") (pintype "passive"))
      (node (ref "R58") (pin "2") (pintype "passive"))
      (node (ref "R68") (pin "2") (pintype "passive"))
      (node (ref "R86") (pin "2") (pintype "passive"))
    )
    (net (code "114") (name "GND") (class "Default")
      (node (ref "C1") (pin "2") (pinfunction "-_2") (pintype "passive"))
      (node (ref "C12") (pin "1") (pintype "passive"))
      (node (ref "C13") (pin "1") (pintype "passive"))
      (node (ref "C14") (pin "1") (pintype "passive"))
      (node (ref "C17") (pin "1") (pintype "passive"))
      (node (ref "C22") (pin "1") (pintype "passive"))
      (node (ref "C23") (pin "1") (pintype "passive"))
      (node (ref "C25") (pin "1") (pintype "passive"))
      (node (ref "C26") (pin "1") (pintype "passive"))
      (node (ref "C28") (pin "2") (pintype "passive"))
      (node (ref "C29") (pin "2") (pintype "passive"))
      (node (ref "C30") (pin "1") (pintype "passive"))
      (node (ref "C31") (pin "1") (pintype "passive"))
      (node (ref "C32") (pin "1") (pintype "passive"))
      (node (ref "C33") (pin "1") (pintype "passive"))
      (node (ref "C34") (pin "1") (pintype "passive"))
      (node (ref "C35") (pin "1") (pintype "passive"))
      (node (ref "C36") (pin "1") (pintype "passive"))
      (node (ref "C37") (pin "1") (pintype "passive"))
      (node (ref "C42") (pin "2") (pintype "passive"))
      (node (ref "C44") (pin "2") (pintype "passive"))
      (node (ref "C45") (pin "1") (pintype "passive"))
      (node (ref "C47") (pin "1") (pintype "passive"))
      (node (ref "C48") (pin "1") (pintype "passive"))
      (node (ref "C49") (pin "1") (pintype "passive"))
      (node (ref "C50") (pin "1") (pintype "passive"))
      (node (ref "C51") (pin "1") (pintype "passive"))
      (node (ref "C52") (pin "1") (pintype "passive"))
      (node (ref "C53") (pin "1") (pintype "passive"))
      (node (ref "C54") (pin "2") (pintype "passive"))
      (node (ref "C55") (pin "1") (pintype "passive"))
      (node (ref "C56") (pin "1") (pintype "passive"))
      (node (ref "C57") (pin "2") (pintype "passive"))
      (node (ref "C58") (pin "1") (pintype "passive"))
      (node (ref "C59") (pin "1") (pintype "passive"))
      (node (ref "C6") (pin "2") (pintype "passive"))
      (node (ref "C60") (pin "1") (pintype "passive"))
      (node (ref "C61") (pin "1") (pintype "passive"))
      (node (ref "C62") (pin "1") (pintype "passive"))
      (node (ref "C63") (pin "2") (pintype "passive"))
      (node (ref "C64") (pin "1") (pintype "passive"))
      (node (ref "C66") (pin "1") (pintype "passive"))
      (node (ref "C67") (pin "1") (pintype "passive"))
      (node (ref "C7") (pin "2") (pintype "passive"))
      (node (ref "C70") (pin "1") (pintype "passive"))
      (node (ref "C71") (pin "1") (pintype "passive"))
      (node (ref "C72") (pin "1") (pintype "passive"))
      (node (ref "C73") (pin "1") (pintype "passive"))
      (node (ref "C74") (pin "2") (pintype "passive"))
      (node (ref "C75") (pin "1") (pintype "passive"))
      (node (ref "C76") (pin "1") (pintype "passive"))
      (node (ref "C77") (pin "1") (pintype "passive"))
      (node (ref "C78") (pin "1") (pintype "passive"))
      (node (ref "C79") (pin "1") (pintype "passive"))
      (node (ref "C80") (pin "1") (pintype "passive"))
      (node (ref "C81") (pin "1") (pintype "passive"))
      (node (ref "C82") (pin "1") (pintype "passive"))
      (node (ref "C83") (pin "1") (pintype "passive"))
      (node (ref "C84") (pin "1") (pintype "passive"))
      (node (ref "C85") (pin "1") (pintype "passive"))
      (node (ref "C86") (pin "1") (pintype "passive"))
      (node (ref "C90") (pin "1") (pintype "passive"))
      (node (ref "CN3") (pin "18") (pinfunction "18_18") (pintype "passive"))
      (node (ref "CN3") (pin "19") (pinfunction "19_19") (pintype "passive"))
      (node (ref "CN3") (pin "2") (pinfunction "2_2") (pintype "passive"))
      (node (ref "CN3") (pin "27") (pinfunction "27_27") (pintype "passive"))
      (node (ref "CN3") (pin "3") (pinfunction "3_3") (pintype "passive"))
      (node (ref "CN4") (pin "1") (pinfunction "1_1") (pintype "passive"))
      (node (ref "CN4") (pin "12") (pinfunction "12_12") (pintype "passive"))
      (node (ref "CN4") (pin "15") (pinfunction "15_15") (pintype "passive"))
      (node (ref "CN4") (pin "16") (pinfunction "16_16") (pintype "passive"))
      (node (ref "CN4") (pin "2") (pinfunction "2_2") (pintype "passive"))
      (node (ref "CN4") (pin "5") (pinfunction "5_5") (pintype "passive"))
      (node (ref "CN4") (pin "6") (pinfunction "6_6") (pintype "passive"))
      (node (ref "CN4") (pin "9") (pinfunction "9_9") (pintype "passive"))
      (node (ref "D10") (pin "3") (pinfunction "K_3") (pintype "passive"))
      (node (ref "D11") (pin "3") (pinfunction "K_3") (pintype "passive"))
      (node (ref "D12") (pin "3") (pinfunction "K_3") (pintype "passive"))
      (node (ref "D13") (pin "2") (pinfunction "2_2") (pintype "passive"))
      (node (ref "D2") (pin "3") (pinfunction "K_3") (pintype "passive"))
      (node (ref "D3") (pin "3") (pinfunction "K_3") (pintype "passive"))
      (node (ref "D4") (pin "3") (pinfunction "K_3") (pintype "passive"))
      (node (ref "D5") (pin "3") (pinfunction "K_3") (pintype "passive"))
      (node (ref "D7") (pin "3") (pinfunction "K_3") (pintype "passive"))
      (node (ref "D8") (pin "3") (pinfunction "K_3") (pintype "passive"))
      (node (ref "D9") (pin "3") (pinfunction "K_3") (pintype "passive"))
      (node (ref "GND") (pin "1") (pinfunction "1_1") (pintype "passive"))
      (node (ref "GND") (pin "2") (pinfunction "2_2") (pintype "passive"))
      (node (ref "GND") (pin "3") (pinfunction "3_3") (pintype "passive"))
      (node (ref "GND") (pin "4") (pinfunction "4_4") (pintype "passive"))
      (node (ref "IC14") (pin "6") (pinfunction "GND_6") (pintype "passive"))
      (node (ref "IC14") (pin "9") (pinfunction "EP_9") (pintype "passive"))
      (node (ref "J12") (pin "1") (pinfunction "1_1") (pintype "passive"))
      (node (ref "J4") (pin "-") (pinfunction "-_-") (pintype "passive"))
      (node (ref "K2") (pin "2") (pinfunction "COIL_2_2") (pintype "passive"))
      (node (ref "LED1") (pin "1") (pintype "passive"))
      (node (ref "R100") (pin "1") (pintype "passive"))
      (node (ref "R101") (pin "1") (pintype "passive"))
      (node (ref "R106") (pin "1") (pintype "passive"))
      (node (ref "R109") (pin "1") (pintype "passive"))
      (node (ref "R112") (pin "1") (pintype "passive"))
      (node (ref "R113") (pin "1") (pintype "passive"))
      (node (ref "R121") (pin "1") (pintype "passive"))
      (node (ref "R124") (pin "1") (pintype "passive"))
      (node (ref "R127") (pin "1") (pintype "passive"))
      (node (ref "R134") (pin "1") (pintype "passive"))
      (node (ref "R135") (pin "1") (pintype "passive"))
      (node (ref "R14") (pin "1") (pintype "passive"))
      (node (ref "R141") (pin "1") (pintype "passive"))
      (node (ref "R146") (pin "1") (pintype "passive"))
      (node (ref "R149") (pin "1") (pintype "passive"))
      (node (ref "R15") (pin "1") (pintype "passive"))
      (node (ref "R20") (pin "1") (pintype "passive"))
      (node (ref "R21") (pin "1") (pintype "passive"))
      (node (ref "R23") (pin "1") (pintype "passive"))
      (node (ref "R24") (pin "1") (pintype "passive"))
      (node (ref "R25") (pin "1") (pintype "passive"))
      (node (ref "R34") (pin "1") (pintype "passive"))
      (node (ref "R39") (pin "1") (pintype "passive"))
      (node (ref "R43") (pin "1") (pintype "passive"))
      (node (ref "R45") (pin "1") (pintype "passive"))
      (node (ref "R48") (pin "1") (pintype "passive"))
      (node (ref "R49") (pin "1") (pintype "passive"))
      (node (ref "R50") (pin "1") (pintype "passive"))
      (node (ref "R52") (pin "1") (pintype "passive"))
      (node (ref "R61") (pin "1") (pintype "passive"))
      (node (ref "R66") (pin "1") (pintype "passive"))
      (node (ref "R70") (pin "1") (pintype "passive"))
      (node (ref "R74") (pin "1") (pintype "passive"))
      (node (ref "R75") (pin "1") (pintype "passive"))
      (node (ref "R76") (pin "1") (pintype "passive"))
      (node (ref "R80") (pin "1") (pintype "passive"))
      (node (ref "R81") (pin "1") (pintype "passive"))
      (node (ref "R89") (pin "1") (pintype "passive"))
      (node (ref "R9") (pin "1") (pintype "passive"))
      (node (ref "R92") (pin "1") (pintype "passive"))
      (node (ref "R96") (pin "1") (pintype "passive"))
      (node (ref "U2") (pin "2") (pinfunction "GND_2") (pintype "passive"))
      (node (ref "U2") (pin "5") (pinfunction "GND_5") (pintype "passive"))
      (node (ref "U4") (pin "2") (pinfunction "GND_2") (pintype "passive"))
      (node (ref "U4") (pin "5") (pinfunction "GND_5") (pintype "passive"))
      (node (ref "U5") (pin "2") (pinfunction "GND_2") (pintype "passive"))
      (node (ref "U5") (pin "5") (pinfunction "GND_5") (pintype "passive"))
      (node (ref "U6") (pin "2") (pinfunction "GND_2") (pintype "passive"))
      (node (ref "U6") (pin "5") (pinfunction "GND_5") (pintype "passive"))
      (node (ref "U7") (pin "2") (pinfunction "GND_2") (pintype "passive"))
      (node (ref "U7") (pin "5") (pinfunction "GND_5") (pintype "passive"))
      (node (ref "ZDB1") (pin "1") (pintype "passive"))
      (node (ref "ZDB10") (pin "1") (pintype "passive"))
      (node (ref "ZDB2") (pin "1") (pintype "passive"))
      (node (ref "ZDB3") (pin "1") (pintype "passive"))
      (node (ref "ZDB4") (pin "1") (pintype "passive"))
      (node (ref "ZDB5") (pin "1") (pintype "passive"))
      (node (ref "ZDB6") (pin "1") (pintype "passive"))
      (node (ref "ZDB7") (pin "1") (pintype "passive"))
      (node (ref "ZDB8") (pin "1") (pintype "passive"))
      (node (ref "ZDB9") (pin "1") (pintype "passive"))
    )
    (net (code "115") (name "Net-(D2-A)") (class "Default")
      (node (ref "D2") (pin "1") (pinfunction "A_1") (pintype "passive"))
      (node (ref "R26") (pin "1") (pintype "passive"))
    )
    (net (code "116") (name "Net-(D3-A)") (class "Default")
      (node (ref "D3") (pin "1") (pinfunction "A_1") (pintype "passive"))
      (node (ref "R27") (pin "2") (pintype "passive"))
    )
    (net (code "117") (name "Net-(D4-A)") (class "Default")
      (node (ref "D4") (pin "1") (pinfunction "A_1") (pintype "passive"))
      (node (ref "R51") (pin "1") (pintype "passive"))
    )
    (net (code "118") (name "Net-(D5-A)") (class "Default")
      (node (ref "D5") (pin "1") (pinfunction "A_1") (pintype "passive"))
      (node (ref "R55") (pin "2") (pintype "passive"))
    )
    (net (code "119") (name "Net-(D7-A)") (class "Default")
      (node (ref "D7") (pin "1") (pinfunction "A_1") (pintype "passive"))
      (node (ref "R77") (pin "1") (pintype "passive"))
    )
    (net (code "120") (name "Net-(D8-A)") (class "Default")
      (node (ref "D8") (pin "1") (pinfunction "A_1") (pintype "passive"))
      (node (ref "R82") (pin "2") (pintype "passive"))
    )
    (net (code "121") (name "Net-(D9-A)") (class "Default")
      (node (ref "D9") (pin "1") (pinfunction "A_1") (pintype "passive"))
      (node (ref "R103") (pin "1") (pintype "passive"))
    )
    (net (code "122") (name "Net-(D10-A)") (class "Default")
      (node (ref "D10") (pin "1") (pinfunction "A_1") (pintype "passive"))
      (node (ref "R118") (pin "2") (pintype "passive"))
    )
    (net (code "123") (name "Net-(D11-A)") (class "Default")
      (node (ref "D11") (pin "1") (pinfunction "A_1") (pintype "passive"))
      (node (ref "R137") (pin "1") (pintype "passive"))
    )
    (net (code "124") (name "Net-(D12-A)") (class "Default")
      (node (ref "D12") (pin "1") (pinfunction "A_1") (pintype "passive"))
      (node (ref "R152") (pin "2") (pintype "passive"))
    )
    (net (code "125") (name "Net-(IC2-DEN)") (class "Default")
      (node (ref "IC2") (pin "6") (pinfunction "DEN_6") (pintype "passive"))
      (node (ref "R3") (pin "1") (pintype "passive"))
    )
    (net (code "126") (name "Net-(IC2-DSEL0)") (class "Default")
      (node (ref "IC2") (pin "8") (pinfunction "DSEL0_8") (pintype "passive"))
      (node (ref "R4") (pin "1") (pintype "passive"))
    )
    (net (code "127") (name "Net-(IC2-DSEL1)") (class "Default")
      (node (ref "IC2") (pin "11") (pinfunction "DSEL1_11") (pintype "passive"))
      (node (ref "R7") (pin "1") (pintype "passive"))
    )
    (net (code "128") (name "Net-(IC2-GND)") (class "Default")
      (node (ref "IC2") (pin "4") (pinfunction "GND_4") (pintype "passive"))
      (node (ref "R26") (pin "2") (pintype "passive"))
    )
    (net (code "129") (name "Net-(IC2-IN0)") (class "Default")
      (node (ref "IC2") (pin "2") (pinfunction "IN0_2") (pintype "passive"))
      (node (ref "R11") (pin "1") (pintype "passive"))
    )
    (net (code "130") (name "Net-(IC2-IN1)") (class "Default")
      (node (ref "IC2") (pin "5") (pinfunction "IN1_5") (pintype "passive"))
      (node (ref "R13") (pin "1") (pintype "passive"))
    )
    (net (code "131") (name "Net-(IC2-IN2)") (class "Default")
      (node (ref "IC2") (pin "9") (pinfunction "IN2_9") (pintype "passive"))
      (node (ref "R17") (pin "1") (pintype "passive"))
    )
    (net (code "132") (name "Net-(IC2-IN3)") (class "Default")
      (node (ref "IC2") (pin "10") (pinfunction "IN3_10") (pintype "passive"))
      (node (ref "R19") (pin "1") (pintype "passive"))
    )
    (net (code "133") (name "Net-(IC2-IS)") (class "Default")
      (node (ref "IC2") (pin "7") (pinfunction "IS_7") (pintype "passive"))
      (node (ref "R22") (pin "1") (pintype "passive"))
      (node (ref "R24") (pin "2") (pintype "passive"))
    )
    (net (code "134") (name "Net-(IC3-DEN)") (class "Default")
      (node (ref "IC3") (pin "3") (pinfunction "DEN_3") (pintype "passive"))
      (node (ref "R5") (pin "1") (pintype "passive"))
    )
    (net (code "135") (name "Net-(IC3-DSEL)") (class "Default")
      (node (ref "IC3") (pin "5") (pinfunction "DSEL_5") (pintype "passive"))
      (node (ref "R8") (pin "1") (pintype "passive"))
    )
    (net (code "136") (name "Net-(IC3-GND)") (class "Default")
      (node (ref "IC3") (pin "1") (pinfunction "GND_1") (pintype "passive"))
      (node (ref "R27") (pin "1") (pintype "passive"))
    )
    (net (code "137") (name "Net-(IC3-IN0)") (class "Default")
      (node (ref "IC3") (pin "2") (pinfunction "IN0_2") (pintype "passive"))
      (node (ref "R12") (pin "1") (pintype "passive"))
    )
    (net (code "138") (name "Net-(IC3-IN1)") (class "Default")
      (node (ref "IC3") (pin "6") (pinfunction "IN1_6") (pintype "passive"))
      (node (ref "R16") (pin "1") (pintype "passive"))
    )
    (net (code "139") (name "Net-(IC3-IS)") (class "Default")
      (node (ref "IC3") (pin "4") (pinfunction "IS_4") (pintype "passive"))
      (node (ref "R18") (pin "1") (pintype "passive"))
      (node (ref "R23") (pin "2") (pintype "passive"))
    )
    (net (code "140") (name "Net-(IC5-DEN)") (class "Default")
      (node (ref "IC5") (pin "6") (pinfunction "DEN_6") (pintype "passive"))
      (node (ref "R29") (pin "1") (pintype "passive"))
    )
    (net (code "141") (name "Net-(IC5-DSEL0)") (class "Default")
      (node (ref "IC5") (pin "8") (pinfunction "DSEL0_8") (pintype "passive"))
      (node (ref "R31") (pin "1") (pintype "passive"))
    )
    (net (code "142") (name "Net-(IC5-DSEL1)") (class "Default")
      (node (ref "IC5") (pin "11") (pinfunction "DSEL1_11") (pintype "passive"))
      (node (ref "R33") (pin "1") (pintype "passive"))
    )
    (net (code "143") (name "Net-(IC5-GND)") (class "Default")
      (node (ref "IC5") (pin "4") (pinfunction "GND_4") (pintype "passive"))
      (node (ref "R51") (pin "2") (pintype "passive"))
    )
    (net (code "144") (name "Net-(IC5-IN0)") (class "Default")
      (node (ref "IC5") (pin "2") (pinfunction "IN0_2") (pintype "passive"))
      (node (ref "R35") (pin "1") (pintype "passive"))
    )
    (net (code "145") (name "Net-(IC5-IN1)") (class "Default")
      (node (ref "IC5") (pin "5") (pinfunction "IN1_5") (pintype "passive"))
      (node (ref "R37") (pin "1") (pintype "passive"))
    )
    (net (code "146") (name "Net-(IC5-IN2)") (class "Default")
      (node (ref "IC5") (pin "9") (pinfunction "IN2_9") (pintype "passive"))
      (node (ref "R40") (pin "1") (pintype "passive"))
    )
    (net (code "147") (name "Net-(IC5-IN3)") (class "Default")
      (node (ref "IC5") (pin "10") (pinfunction "IN3_10") (pintype "passive"))
      (node (ref "R42") (pin "1") (pintype "passive"))
    )
    (net (code "148") (name "Net-(IC5-IS)") (class "Default")
      (node (ref "IC5") (pin "7") (pinfunction "IS_7") (pintype "passive"))
      (node (ref "R46") (pin "1") (pintype "passive"))
      (node (ref "R49") (pin "2") (pintype "passive"))
    )
    (net (code "149") (name "Net-(IC6-DEN)") (class "Default")
      (node (ref "IC6") (pin "3") (pinfunction "DEN_3") (pintype "passive"))
      (node (ref "R36") (pin "1") (pintype "passive"))
    )
    (net (code "150") (name "Net-(IC6-DSEL)") (class "Default")
      (node (ref "IC6") (pin "5") (pinfunction "DSEL_5") (pintype "passive"))
      (node (ref "R38") (pin "1") (pintype "passive"))
    )
    (net (code "151") (name "Net-(IC6-GND)") (class "Default")
      (node (ref "IC6") (pin "1") (pinfunction "GND_1") (pintype "passive"))
      (node (ref "R55") (pin "1") (pintype "passive"))
    )
    (net (code "152") (name "Net-(IC6-IN0)") (class "Default")
      (node (ref "IC6") (pin "2") (pinfunction "IN0_2") (pintype "passive"))
      (node (ref "R41") (pin "1") (pintype "passive"))
    )
    (net (code "153") (name "Net-(IC6-IN1)") (class "Default")
      (node (ref "IC6") (pin "6") (pinfunction "IN1_6") (pintype "passive"))
      (node (ref "R44") (pin "1") (pintype "passive"))
    )
    (net (code "154") (name "Net-(IC6-IS)") (class "Default")
      (node (ref "IC6") (pin "4") (pinfunction "IS_4") (pintype "passive"))
      (node (ref "R47") (pin "1") (pintype "passive"))
      (node (ref "R52") (pin "2") (pintype "passive"))
    )
    (net (code "155") (name "Net-(IC7-DEN)") (class "Default")
      (node (ref "IC7") (pin "6") (pinfunction "DEN_6") (pintype "passive"))
      (node (ref "R58") (pin "1") (pintype "passive"))
    )
    (net (code "156") (name "Net-(IC7-DSEL0)") (class "Default")
      (node (ref "IC7") (pin "8") (pinfunction "DSEL0_8") (pintype "passive"))
      (node (ref "R59") (pin "1") (pintype "passive"))
    )
    (net (code "157") (name "Net-(IC7-DSEL1)") (class "Default")
      (node (ref "IC7") (pin "11") (pinfunction "DSEL1_11") (pintype "passive"))
      (node (ref "R60") (pin "1") (pintype "passive"))
    )
    (net (code "158") (name "Net-(IC7-GND)") (class "Default")
      (node (ref "IC7") (pin "4") (pinfunction "GND_4") (pintype "passive"))
      (node (ref "R77") (pin "2") (pintype "passive"))
    )
    (net (code "159") (name "Net-(IC7-IN0)") (class "Default")
      (node (ref "IC7") (pin "2") (pinfunction "IN0_2") (pintype "passive"))
      (node (ref "R63") (pin "1") (pintype "passive"))
    )
    (net (code "160") (name "Net-(IC7-IN1)") (class "Default")
      (node (ref "IC7") (pin "5") (pinfunction "IN1_5") (pintype "passive"))
      (node (ref "R65") (pin "1") (pintype "passive"))
    )
    (net (code "161") (name "Net-(IC7-IN2)") (class "Default")
      (node (ref "IC7") (pin "9") (pinfunction "IN2_9") (pintype "passive"))
      (node (ref "R67") (pin "1") (pintype "passive"))
    )
    (net (code "162") (name "Net-(IC7-IN3)") (class "Default")
      (node (ref "IC7") (pin "10") (pinfunction "IN3_10") (pintype "passive"))
      (node (ref "R69") (pin "1") (pintype "passive"))
    )
    (net (code "163") (name "Net-(IC7-IS)") (class "Default")
      (node (ref "IC7") (pin "7") (pinfunction "IS_7") (pintype "passive"))
      (node (ref "R72") (pin "1") (pintype "passive"))
      (node (ref "R74") (pin "2") (pintype "passive"))
    )
    (net (code "164") (name "Net-(IC9-DEN)") (class "Default")
      (node (ref "IC9") (pin "3") (pinfunction "DEN_3") (pintype "passive"))
      (node (ref "R68") (pin "1") (pintype "passive"))
    )
    (net (code "165") (name "Net-(IC9-DSEL)") (class "Default")
      (node (ref "IC9") (pin "5") (pinfunction "DSEL_5") (pintype "passive"))
      (node (ref "R71") (pin "1") (pintype "passive"))
    )
    (net (code "166") (name "Net-(IC9-GND)") (class "Default")
      (node (ref "IC9") (pin "1") (pinfunction "GND_1") (pintype "passive"))
      (node (ref "R82") (pin "1") (pintype "passive"))
    )
    (net (code "167") (name "Net-(IC9-IN0)") (class "Default")
      (node (ref "IC9") (pin "2") (pinfunction "IN0_2") (pintype "passive"))
      (node (ref "R73") (pin "1") (pintype "passive"))
    )
    (net (code "168") (name "Net-(IC9-IN1)") (class "Default")
      (node (ref "IC9") (pin "6") (pinfunction "IN1_6") (pintype "passive"))
      (node (ref "R78") (pin "1") (pintype "passive"))
    )
    (net (code "169") (name "Net-(IC9-IS)") (class "Default")
      (node (ref "IC9") (pin "4") (pinfunction "IS_4") (pintype "passive"))
      (node (ref "R79") (pin "1") (pintype "passive"))
      (node (ref "R81") (pin "2") (pintype "passive"))
    )
    (net (code "170") (name "Net-(IC10-DEN)") (class "Default")
      (node (ref "IC10") (pin "6") (pinfunction "DEN_6") (pintype "passive"))
      (node (ref "R86") (pin "1") (pintype "passive"))
    )
    (net (code "171") (name "Net-(IC10-DSEL0)") (class "Default")
      (node (ref "IC10") (pin "8") (pinfunction "DSEL0_8") (pintype "passive"))
      (node (ref "R87") (pin "1") (pintype "passive"))
    )
    (net (code "172") (name "Net-(IC10-DSEL1)") (class "Default")
      (node (ref "IC10") (pin "11") (pinfunction "DSEL1_11") (pintype "passive"))
      (node (ref "R88") (pin "1") (pintype "passive"))
    )
    (net (code "173") (name "Net-(IC10-GND)") (class "Default")
      (node (ref "IC10") (pin "4") (pinfunction "GND_4") (pintype "passive"))
      (node (ref "R103") (pin "2") (pintype "passive"))
    )
    (net (code "174") (name "Net-(IC10-IN0)") (class "Default")
      (node (ref "IC10") (pin "2") (pinfunction "IN0_2") (pintype "passive"))
      (node (ref "R90") (pin "1") (pintype "passive"))
    )
    (net (code "175") (name "Net-(IC10-IN1)") (class "Default")
      (node (ref "IC10") (pin "5") (pinfunction "IN1_5") (pintype "passive"))
      (node (ref "R91") (pin "1") (pintype "passive"))
    )
    (net (code "176") (name "Net-(IC10-IN2)") (class "Default")
      (node (ref "IC10") (pin "9") (pinfunction "IN2_9") (pintype "passive"))
      (node (ref "R93") (pin "1") (pintype "passive"))
    )
    (net (code "177") (name "Net-(IC10-IN3)") (class "Default")
      (node (ref "IC10") (pin "10") (pinfunction "IN3_10") (pintype "passive"))
      (node (ref "R95") (pin "1") (pintype "passive"))
    )
    (net (code "178") (name "Net-(IC10-IS)") (class "Default")
      (node (ref "IC10") (pin "7") (pinfunction "IS_7") (pintype "passive"))
      (node (ref "R100") (pin "2") (pintype "passive"))
      (node (ref "R98") (pin "1") (pintype "passive"))
    )
    (net (code "179") (name "Net-(IC11-DEN)") (class "Default")
      (node (ref "IC11") (pin "3") (pinfunction "DEN_3") (pintype "passive"))
      (node (ref "R102") (pin "1") (pintype "passive"))
    )
    (net (code "180") (name "Net-(IC11-DSEL)") (class "Default")
      (node (ref "IC11") (pin "5") (pinfunction "DSEL_5") (pintype "passive"))
      (node (ref "R104") (pin "1") (pintype "passive"))
    )
    (net (code "181") (name "Net-(IC11-GND)") (class "Default")
      (node (ref "IC11") (pin "1") (pinfunction "GND_1") (pintype "passive"))
      (node (ref "R118") (pin "1") (pintype "passive"))
    )
    (net (code "182") (name "Net-(IC11-IN0)") (class "Default")
      (node (ref "IC11") (pin "2") (pinfunction "IN0_2") (pintype "passive"))
      (node (ref "R105") (pin "1") (pintype "passive"))
    )
    (net (code "183") (name "Net-(IC11-IN1)") (class "Default")
      (node (ref "IC11") (pin "6") (pinfunction "IN1_6") (pintype "passive"))
      (node (ref "R107") (pin "1") (pintype "passive"))
    )
    (net (code "184") (name "Net-(IC11-IS)") (class "Default")
      (node (ref "IC11") (pin "4") (pinfunction "IS_4") (pintype "passive"))
      (node (ref "R108") (pin "1") (pintype "passive"))
      (node (ref "R112") (pin "2") (pintype "passive"))
    )
    (net (code "185") (name "Net-(IC12-DEN)") (class "Default")
      (node (ref "IC12") (pin "6") (pinfunction "DEN_6") (pintype "passive"))
      (node (ref "R117") (pin "1") (pintype "passive"))
    )
    (net (code "186") (name "Net-(IC12-DSEL0)") (class "Default")
      (node (ref "IC12") (pin "8") (pinfunction "DSEL0_8") (pintype "passive"))
      (node (ref "R119") (pin "1") (pintype "passive"))
    )
    (net (code "187") (name "Net-(IC12-DSEL1)") (class "Default")
      (node (ref "IC12") (pin "11") (pinfunction "DSEL1_11") (pintype "passive"))
      (node (ref "R120") (pin "1") (pintype "passive"))
    )
    (net (code "188") (name "Net-(IC12-GND)") (class "Default")
      (node (ref "IC12") (pin "4") (pinfunction "GND_4") (pintype "passive"))
      (node (ref "R137") (pin "2") (pintype "passive"))
    )
    (net (code "189") (name "Net-(IC12-IN0)") (class "Default")
      (node (ref "IC12") (pin "2") (pinfunction "IN0_2") (pintype "passive"))
      (node (ref "R122") (pin "1") (pintype "passive"))
    )
    (net (code "190") (name "Net-(IC12-IN1)") (class "Default")
      (node (ref "IC12") (pin "5") (pinfunction "IN1_5") (pintype "passive"))
      (node (ref "R123") (pin "1") (pintype "passive"))
    )
    (net (code "191") (name "Net-(IC12-IN2)") (class "Default")
      (node (ref "IC12") (pin "9") (pinfunction "IN2_9") (pintype "passive"))
      (node (ref "R125") (pin "1") (pintype "passive"))
    )
    (net (code "192") (name "Net-(IC12-IN3)") (class "Default")
      (node (ref "IC12") (pin "10") (pinfunction "IN3_10") (pintype "passive"))
      (node (ref "R126") (pin "1") (pintype "passive"))
    )
    (net (code "193") (name "Net-(IC12-IS)") (class "Default")
      (node (ref "IC12") (pin "7") (pinfunction "IS_7") (pintype "passive"))
      (node (ref "R130") (pin "1") (pintype "passive"))
      (node (ref "R134") (pin "2") (pintype "passive"))
    )
    (net (code "194") (name "Net-(IC13-DEN)") (class "Default")
      (node (ref "IC13") (pin "3") (pinfunction "DEN_3") (pintype "passive"))
      (node (ref "R138") (pin "1") (pintype "passive"))
    )
    (net (code "195") (name "Net-(IC13-DSEL)") (class "Default")
      (node (ref "IC13") (pin "5") (pinfunction "DSEL_5") (pintype "passive"))
      (node (ref "R139") (pin "1") (pintype "passive"))
    )
    (net (code "196") (name "Net-(IC13-GND)") (class "Default")
      (node (ref "IC13") (pin "1") (pinfunction "GND_1") (pintype "passive"))
      (node (ref "R152") (pin "1") (pintype "passive"))
    )
    (net (code "197") (name "Net-(IC13-IN0)") (class "Default")
      (node (ref "IC13") (pin "2") (pinfunction "IN0_2") (pintype "passive"))
      (node (ref "R140") (pin "1") (pintype "passive"))
    )
    (net (code "198") (name "Net-(IC13-IN1)") (class "Default")
      (node (ref "IC13") (pin "6") (pinfunction "IN1_6") (pintype "passive"))
      (node (ref "R142") (pin "1") (pintype "passive"))
    )
    (net (code "199") (name "Net-(IC13-IS)") (class "Default")
      (node (ref "IC13") (pin "4") (pinfunction "IS_4") (pintype "passive"))
      (node (ref "R145") (pin "1") (pintype "passive"))
      (node (ref "R149") (pin "2") (pintype "passive"))
    )
    (net (code "200") (name "Net-(IC14-BOOT)") (class "Default")
      (node (ref "C68") (pin "1") (pintype "passive"))
      (node (ref "IC14") (pin "1") (pinfunction "BOOT_1") (pintype "passive"))
    )
    (net (code "201") (name "Net-(IC14-PH)") (class "Default")
      (node (ref "C68") (pin "2") (pintype "passive"))
      (node (ref "D13") (pin "1") (pinfunction "1_1") (pintype "passive"))
      (node (ref "IC14") (pin "8") (pinfunction "PH_8") (pintype "passive"))
      (node (ref "L1") (pin "1") (pinfunction "1_1") (pintype "passive"))
    )
    (net (code "202") (name "Net-(IC14-VSENSE)") (class "Default")
      (node (ref "IC14") (pin "4") (pinfunction "VSENSE_4") (pintype "passive"))
      (node (ref "R113") (pin "2") (pintype "passive"))
      (node (ref "R2") (pin "1") (pintype "passive"))
    )
    (net (code "203") (name "Net-(K1-NO_1)") (class "Default")
      (node (ref "FU1") (pin "2") (pintype "passive"))
      (node (ref "K1") (pin "1") (pinfunction "NO_1_1") (pintype "passive"))
    )
    (net (code "204") (name "Net-(LED1-Pad2)") (class "Default")
      (node (ref "LED1") (pin "2") (pintype "passive"))
      (node (ref "R32") (pin "1") (pintype "passive"))
    )
    (net (code "205") (name "Net-(U2-+Vo)") (class "Default")
      (node (ref "C66") (pin "2") (pintype "passive"))
      (node (ref "R111") (pin "1") (pintype "passive"))
      (node (ref "U2") (pin "3") (pinfunction "+Vo_3") (pintype "passive"))
    )
    (net (code "206") (name "Net-(U4-+Vo)") (class "Default")
      (node (ref "C70") (pin "2") (pintype "passive"))
      (node (ref "R114") (pin "1") (pintype "passive"))
      (node (ref "U4") (pin "3") (pinfunction "+Vo_3") (pintype "passive"))
    )
    (net (code "207") (name "Net-(U5-+Vo)") (class "Default")
      (node (ref "C76") (pin "2") (pintype "passive"))
      (node (ref "R129") (pin "1") (pintype "passive"))
      (node (ref "U5") (pin "3") (pinfunction "+Vo_3") (pintype "passive"))
    )
    (net (code "208") (name "Net-(U6-+Vo)") (class "Default")
      (node (ref "C79") (pin "2") (pintype "passive"))
      (node (ref "R131") (pin "1") (pintype "passive"))
      (node (ref "U6") (pin "3") (pinfunction "+Vo_3") (pintype "passive"))
    )
    (net (code "209") (name "Net-(U7-+Vo)") (class "Default")
      (node (ref "C82") (pin "2") (pintype "passive"))
      (node (ref "R133") (pin "1") (pintype "passive"))
      (node (ref "U7") (pin "3") (pinfunction "+Vo_3") (pintype "passive"))
    )
    (net (code "210") (name "VBAT") (class "Default")
      (node (ref "CN4") (pin "19") (pinfunction "19_19") (pintype "passive"))
      (node (ref "CN4") (pin "20") (pinfunction "20_20") (pintype "passive"))
      (node (ref "FU2") (pin "2") (pintype "passive"))
      (node (ref "J12") (pin "2") (pinfunction "2_2") (pintype "passive"))
      (node (ref "K1") (pin "4") (pinfunction "COM_2_4") (pintype "passive"))
      (node (ref "VBAT1") (pin "1") (pinfunction "1_1") (pintype "passive"))
      (node (ref "VBAT1") (pin "2") (pinfunction "2_2") (pintype "passive"))
      (node (ref "VBAT1") (pin "3") (pinfunction "3_3") (pintype "passive"))
      (node (ref "VBAT1") (pin "4") (pinfunction "4_4") (pintype "passive"))
      (node (ref "VBAT2") (pin "1") (pinfunction "1_1") (pintype "passive"))
      (node (ref "VBAT2") (pin "2") (pinfunction "2_2") (pintype "passive"))
      (node (ref "VBAT2") (pin "3") (pinfunction "3_3") (pintype "passive"))
      (node (ref "VBAT2") (pin "4") (pinfunction "4_4") (pintype "passive"))
    )
    (net (code "211") (name "unconnected-(HIGH-Pad1)") (class "Default")
      (node (ref "HIGH") (pin "1") (pinfunction "1_1") (pintype "passive"))
    )
    (net (code "212") (name "unconnected-(HIGH-Pad2)") (class "Default")
      (node (ref "HIGH") (pin "2") (pinfunction "2_2") (pintype "passive"))
    )
    (net (code "213") (name "unconnected-(HIGH-Pad10)") (class "Default")
      (node (ref "HIGH") (pin "10") (pinfunction "10_10") (pintype "passive"))
    )
    (net (code "214") (name "unconnected-(HIGH-Pad11)") (class "Default")
      (node (ref "HIGH") (pin "11") (pinfunction "11_11") (pintype "passive"))
    )
    (net (code "215") (name "unconnected-(IC14-ENA-Pad5)") (class "Default")
      (node (ref "IC14") (pin "5") (pinfunction "ENA_5") (pintype "passive"))
    )
    (net (code "216") (name "unconnected-(IC14-NC_1-Pad2)") (class "Default")
      (node (ref "IC14") (pin "2") (pinfunction "NC_1_2") (pintype "passive"))
    )
    (net (code "217") (name "unconnected-(IC14-NC_2-Pad3)") (class "Default")
      (node (ref "IC14") (pin "3") (pinfunction "NC_2_3") (pintype "passive"))
    )
    (net (code "218") (name "unconnected-(J12-Pad3)") (class "Default")
      (node (ref "J12") (pin "3") (pinfunction "3_3") (pintype "passive+no_connect"))
    )
    (net (code "219") (name "unconnected-(J12-Pad4)") (class "Default")
      (node (ref "J12") (pin "4") (pinfunction "4_4") (pintype "passive+no_connect"))
    )
    (net (code "220") (name "unconnected-(K1-COM_1-Pad3)") (class "Default")
      (node (ref "K1") (pin "3") (pinfunction "COM_1_3") (pintype "passive"))
    )
    (net (code "221") (name "unconnected-(K1-NO_2-Pad2)") (class "Default")
      (node (ref "K1") (pin "2") (pinfunction "NO_2_2") (pintype "passive"))
    )
    (net (code "222") (name "unconnected-(LOW1-Pad3)") (class "Default")
      (node (ref "LOW1") (pin "3") (pinfunction "3_3") (pintype "passive"))
    )
    (net (code "223") (name "unconnected-(LOW1-Pad13)") (class "Default")
      (node (ref "LOW1") (pin "13") (pinfunction "13_13") (pintype "passive"))
    )
    (net (code "224") (name "unconnected-(LOW1-Pad21)") (class "Default")
      (node (ref "LOW1") (pin "21") (pinfunction "21_21") (pintype "passive"))
    )
    (net (code "225") (name "unconnected-(LOW1-Pad22)") (class "Default")
      (node (ref "LOW1") (pin "22") (pinfunction "22_22") (pintype "passive"))
    )
    (net (code "226") (name "unconnected-(LOW2-Pad19)") (class "Default")
      (node (ref "LOW2") (pin "19") (pinfunction "19_19") (pintype "passive"))
    )
    (net (code "227") (name "unconnected-(LOW2-Pad20)") (class "Default")
      (node (ref "LOW2") (pin "20") (pinfunction "20_20") (pintype "passive"))
    )
    (net (code "228") (name "unconnected-(U2-Trim-Pad4)") (class "Default")
      (node (ref "U2") (pin "4") (pinfunction "Trim_4") (pintype "passive"))
    )
    (net (code "229") (name "unconnected-(U4-Trim-Pad4)") (class "Default")
      (node (ref "U4") (pin "4") (pinfunction "Trim_4") (pintype "passive"))
    )
    (net (code "230") (name "unconnected-(U5-Trim-Pad4)") (class "Default")
      (node (ref "U5") (pin "4") (pinfunction "Trim_4") (pintype "passive"))
    )
    (net (code "231") (name "unconnected-(U6-Trim-Pad4)") (class "Default")
      (node (ref "U6") (pin "4") (pinfunction "Trim_4") (pintype "passive"))
    )
    (net (code "232") (name "unconnected-(U7-Trim-Pad4)") (class "Default")
      (node (ref "U7") (pin "4") (pinfunction "Trim_4") (pintype "passive"))
    )
  )
)
